# cutdown.net
KiCad netlist of a schematic drawn in EAGLE
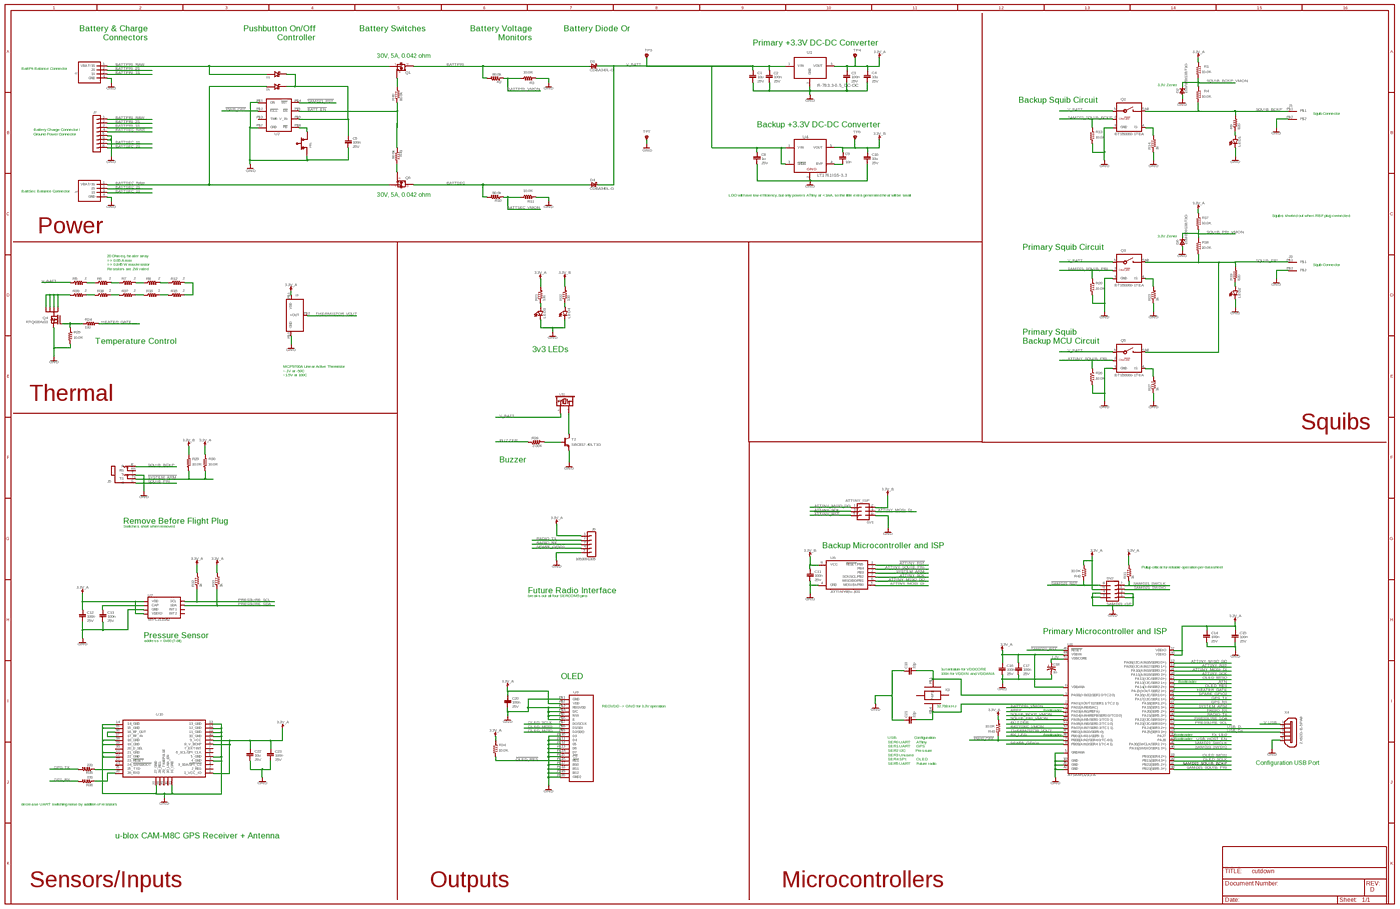
[diagram p0: schematic, sheet 1, overview]
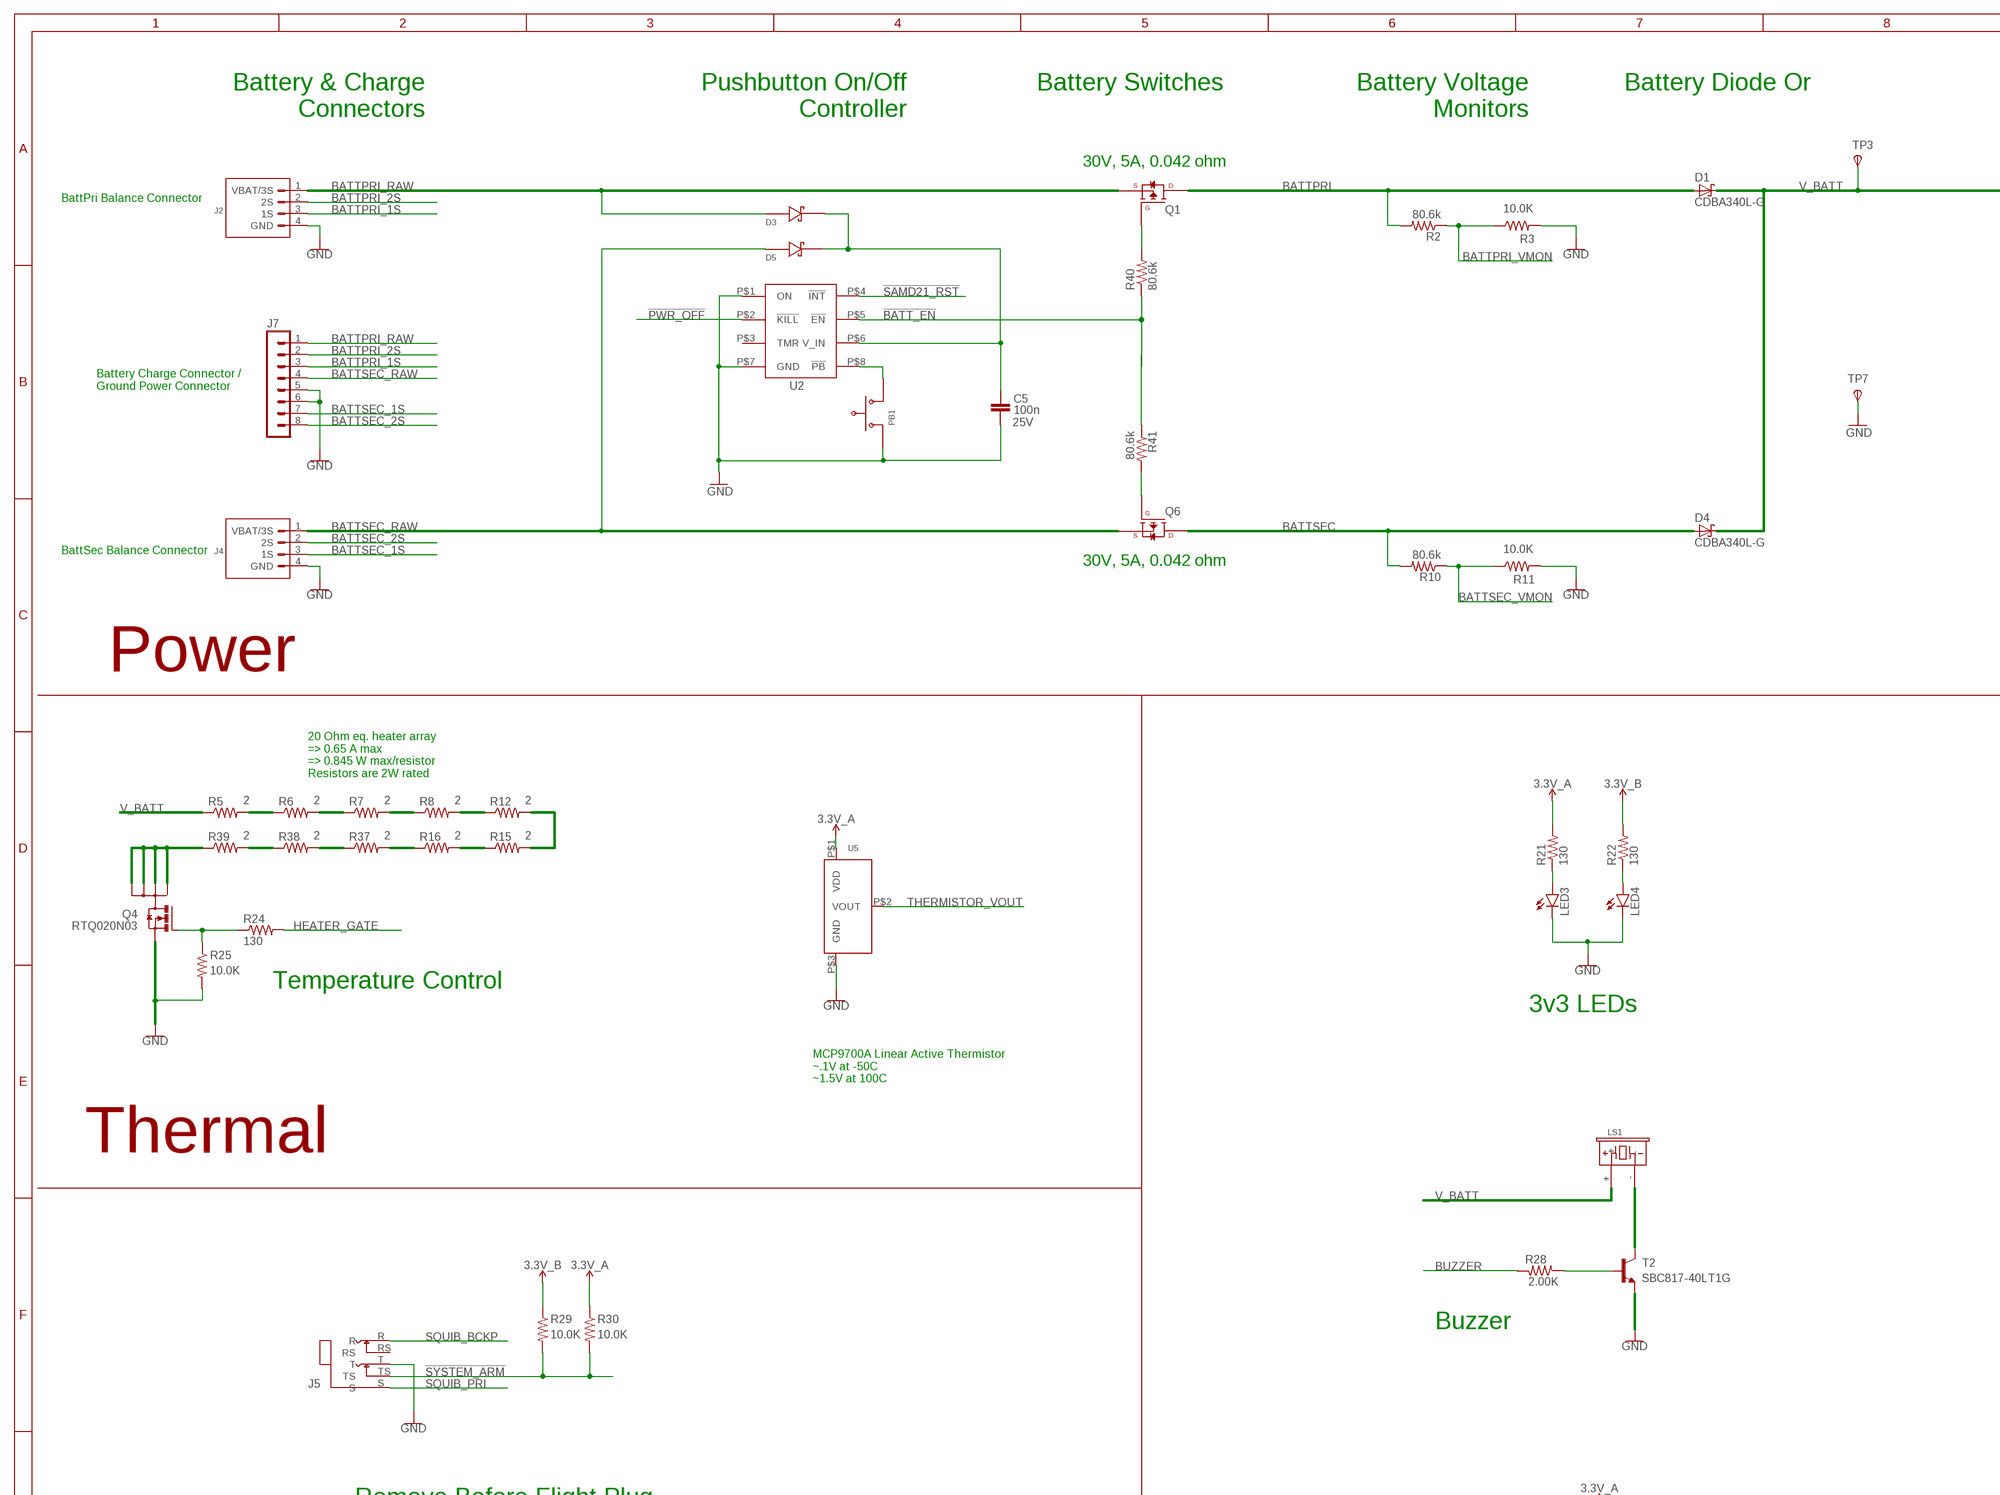
[diagram p1: schematic, sheet 1, part 1 of 4]
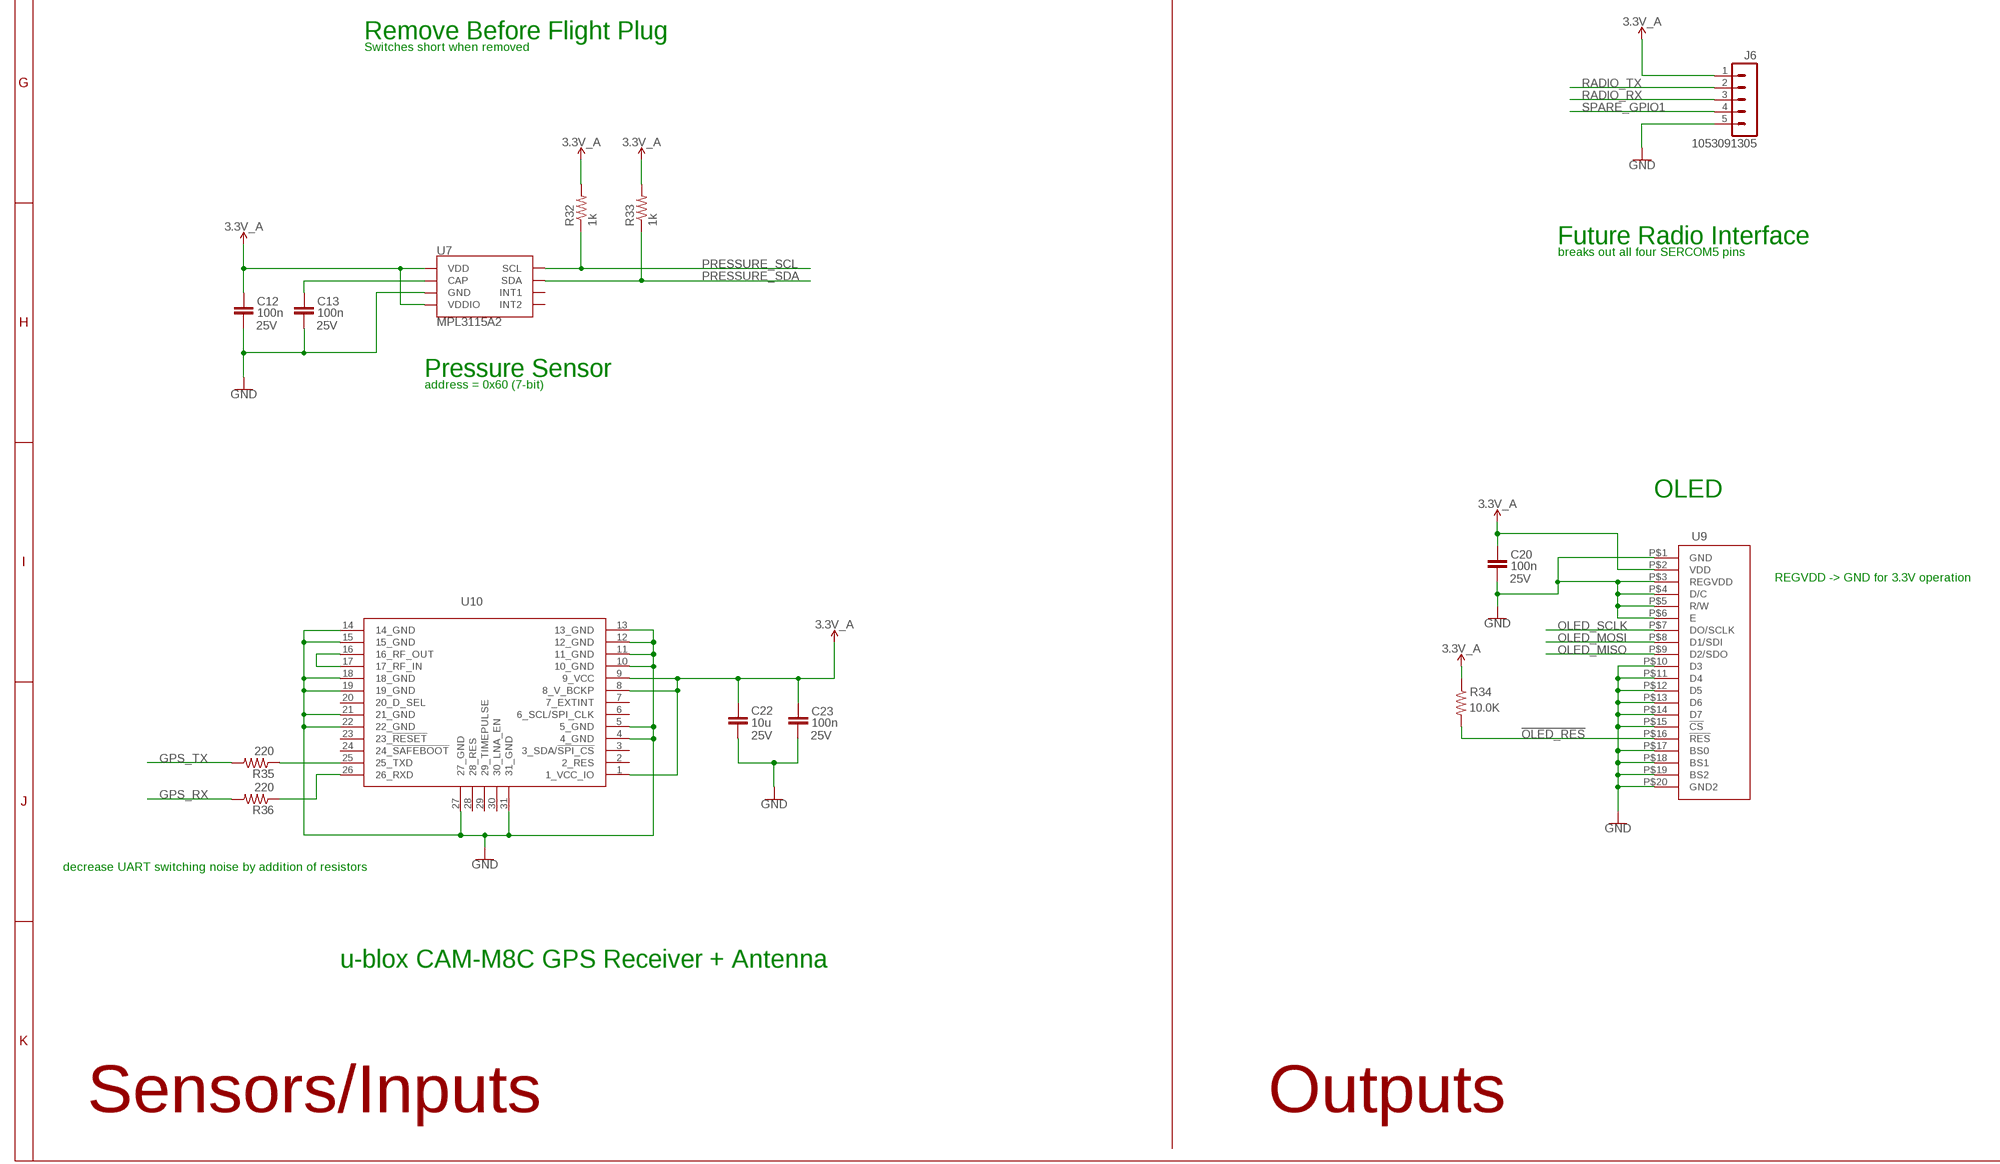
[diagram p2: schematic, sheet 1, part 2 of 4]
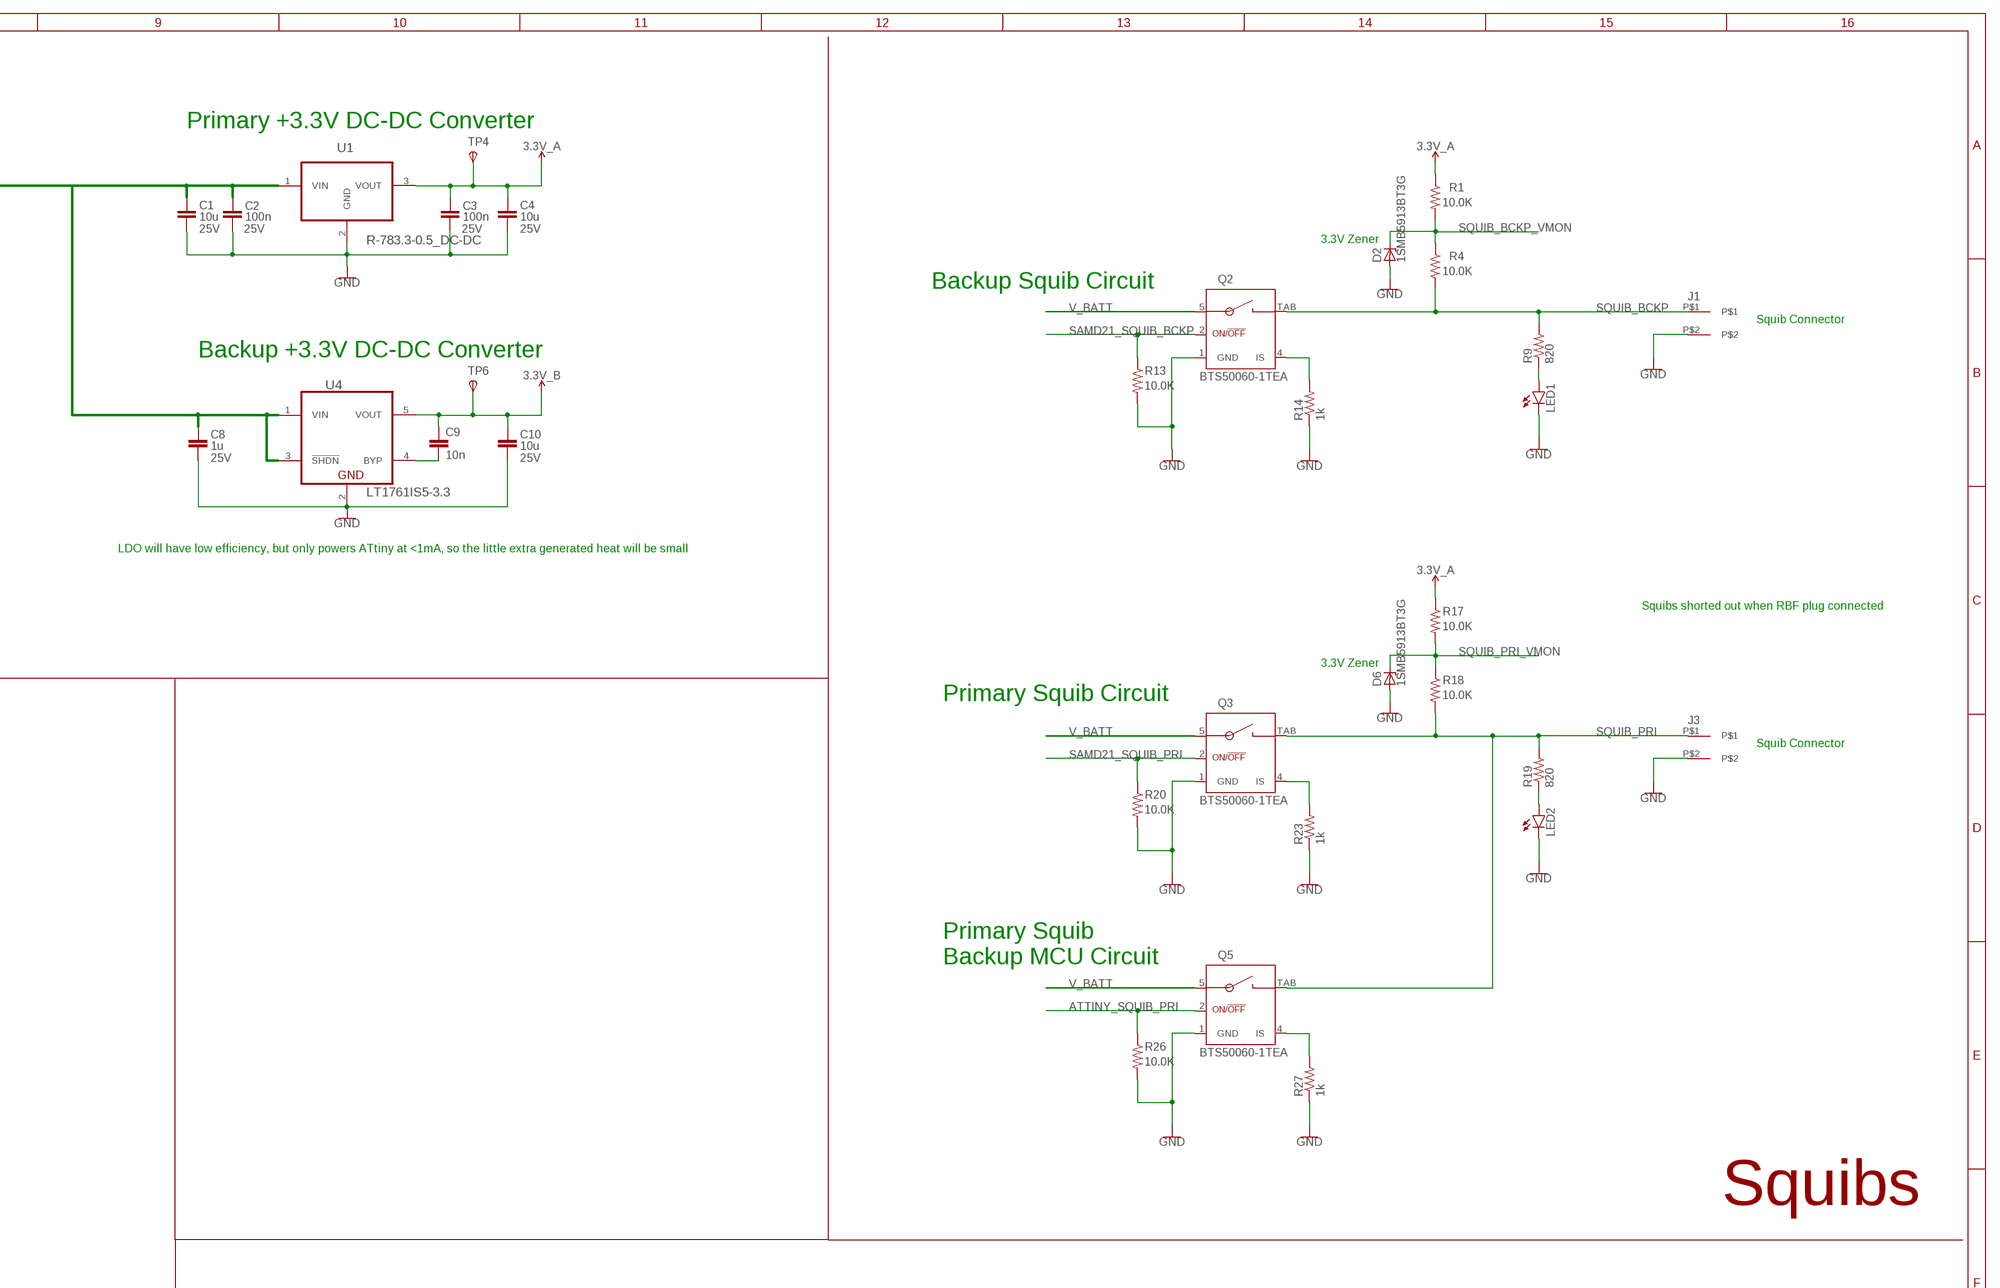
[diagram p3: schematic, sheet 1, part 3 of 4]
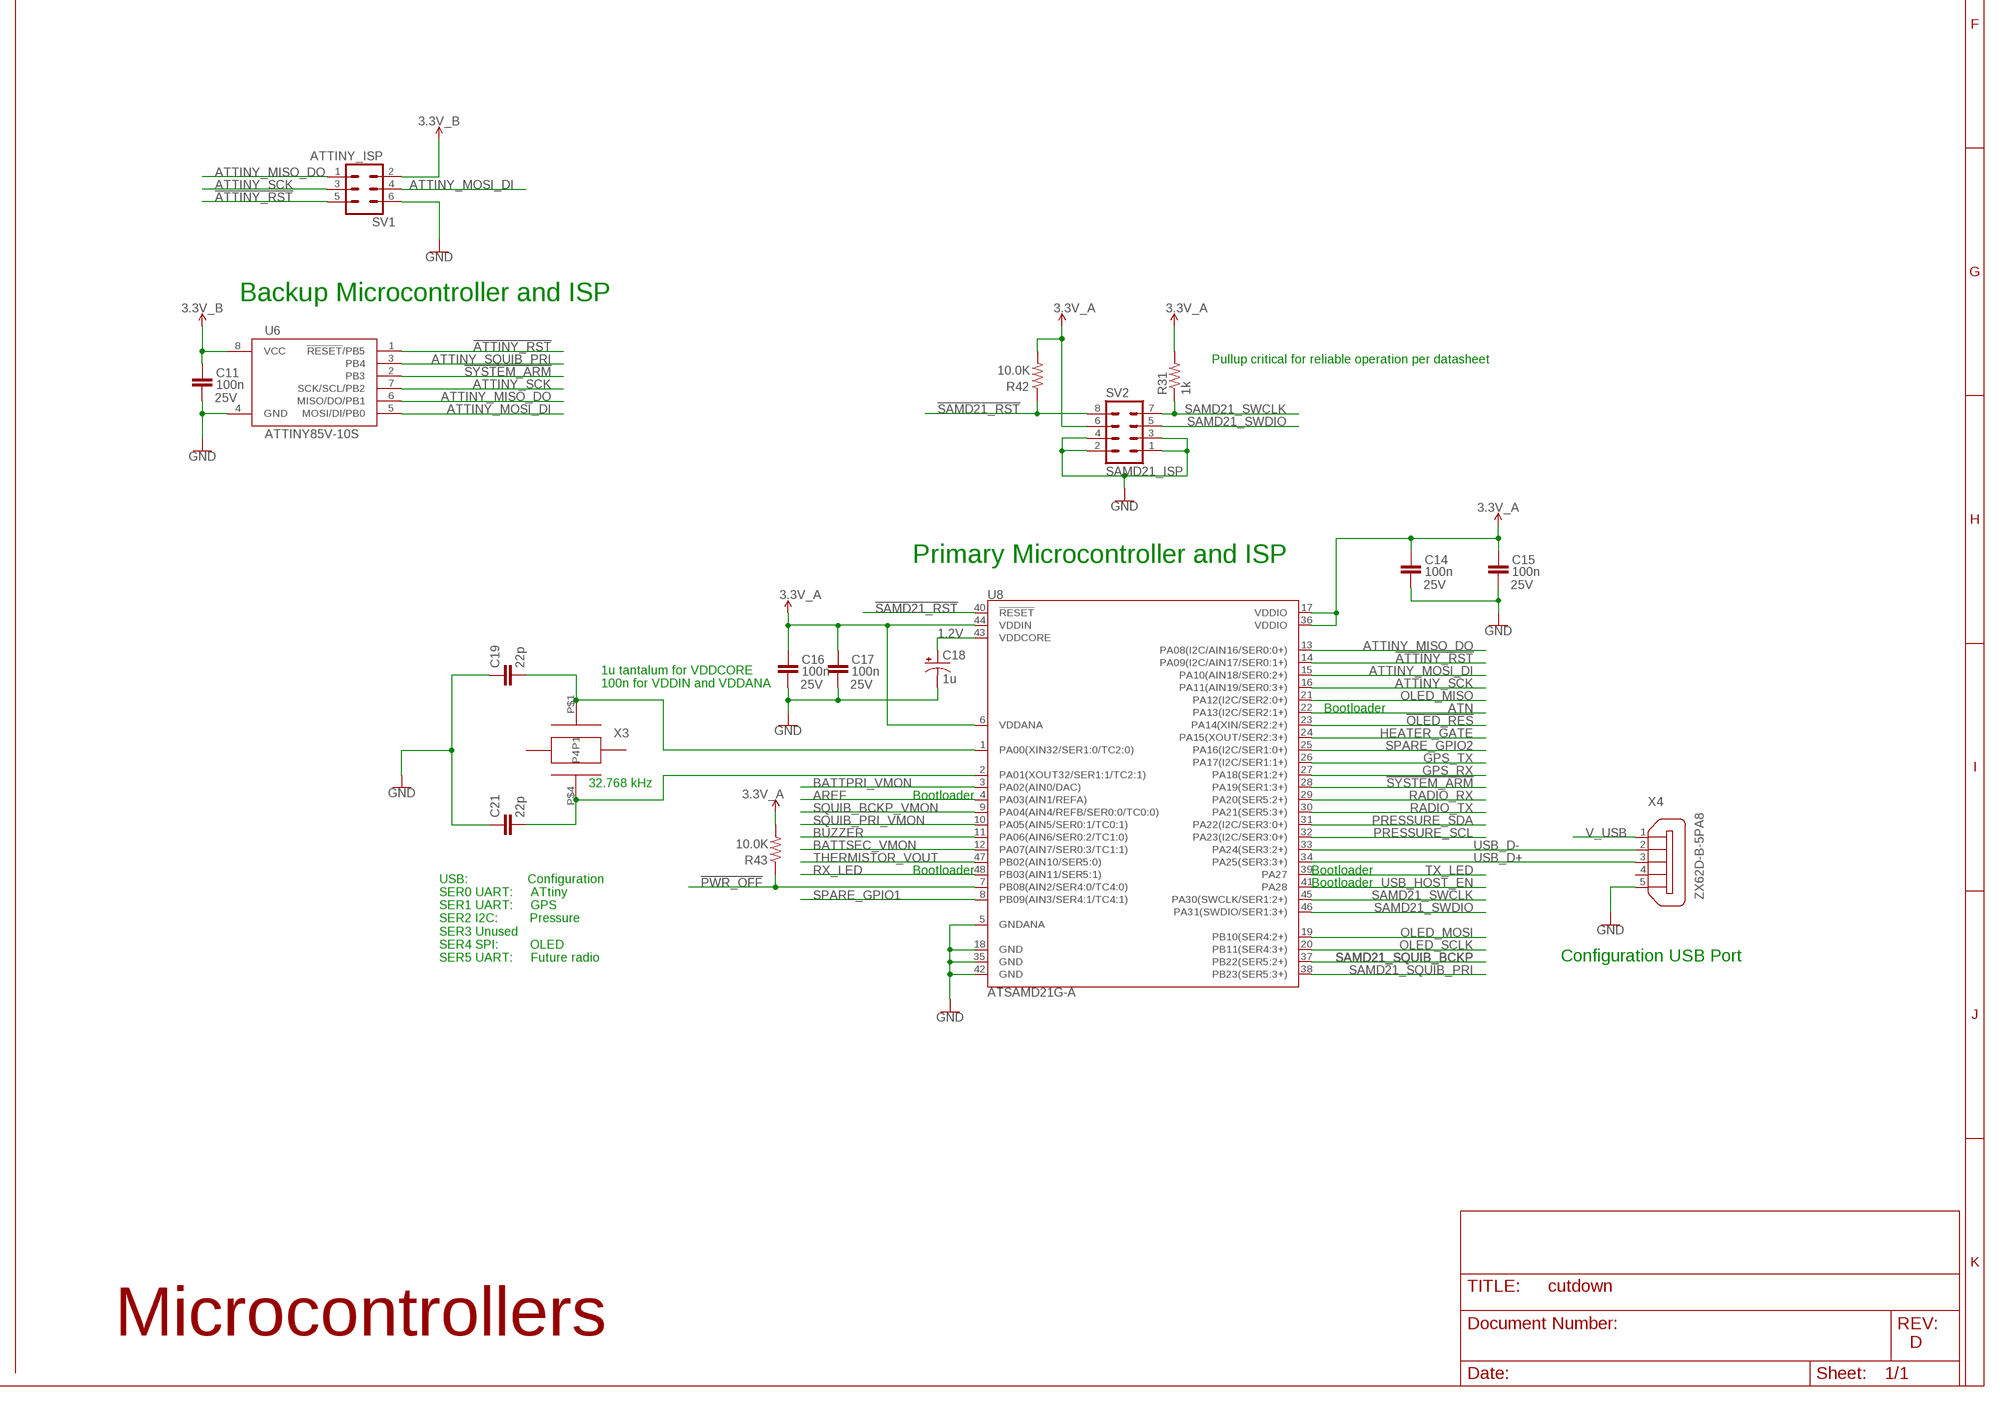
[diagram p4: schematic, sheet 1, part 4 of 4]

(export (version "E")
  (design (tool "Eeschema 10.0.6"))
  (components
    (comp (ref "C1")
      (value "10u")
      (footprint "eagle-import:C1206")
      (fields (field (name "MFG") "Samsung") (field (name "VOLTAGE") "25V"))
      (libsource (lib "eagle-import") (part "C-EUC1206"))
    )
    (comp (ref "C2")
      (value "100n")
      (footprint "eagle-import:C0805")
      (fields (field (name "MFG") "AVX") (field (name "VOLTAGE") "25V"))
      (libsource (lib "eagle-import") (part "resistor_348_C-EUC0805"))
    )
    (comp (ref "C3")
      (value "100n")
      (footprint "eagle-import:C0805")
      (fields (field (name "MFG") "AVX") (field (name "VOLTAGE") "25V"))
      (libsource (lib "eagle-import") (part "resistor_348_C-EUC0805"))
    )
    (comp (ref "C4")
      (value "10u")
      (footprint "eagle-import:C1206")
      (fields (field (name "MFG") "Samsung") (field (name "VOLTAGE") "25V"))
      (libsource (lib "eagle-import") (part "C-EUC1206"))
    )
    (comp (ref "C5")
      (value "100n")
      (footprint "eagle-import:C0805")
      (fields (field (name "MFG") "AVX") (field (name "VOLTAGE") "25V"))
      (libsource (lib "eagle-import") (part "resistor_348_C-EUC0805"))
    )
    (comp (ref "C8")
      (value "1u")
      (footprint "eagle-import:C1206")
      (fields (field (name "MFG") "KEMET") (field (name "VOLTAGE") "25V"))
      (libsource (lib "eagle-import") (part "C-EUC1206"))
    )
    (comp (ref "C9")
      (value "10n")
      (footprint "eagle-import:C0805")
      (fields (field (name "MFG") "Kemet"))
      (libsource (lib "eagle-import") (part "rcl_334_C-EUC0805"))
    )
    (comp (ref "C10")
      (value "10u")
      (footprint "eagle-import:C1206")
      (fields (field (name "MFG") "Samsung") (field (name "VOLTAGE") "25V"))
      (libsource (lib "eagle-import") (part "C-EUC1206"))
    )
    (comp (ref "C11")
      (value "100n")
      (footprint "eagle-import:C0805")
      (fields (field (name "MFG") "AVX") (field (name "VOLTAGE") "25V"))
      (libsource (lib "eagle-import") (part "resistor_348_C-EUC0805"))
    )
    (comp (ref "C12")
      (value "100n")
      (footprint "eagle-import:C0805")
      (fields (field (name "MFG") "AVX") (field (name "VOLTAGE") "25V"))
      (libsource (lib "eagle-import") (part "resistor_348_C-EUC0805"))
    )
    (comp (ref "C13")
      (value "100n")
      (footprint "eagle-import:C0805")
      (fields (field (name "MFG") "AVX") (field (name "VOLTAGE") "25V"))
      (libsource (lib "eagle-import") (part "resistor_348_C-EUC0805"))
    )
    (comp (ref "C14")
      (value "100n")
      (footprint "eagle-import:C0805")
      (fields (field (name "MFG") "AVX") (field (name "VOLTAGE") "25V"))
      (libsource (lib "eagle-import") (part "resistor_348_C-EUC0805"))
    )
    (comp (ref "C15")
      (value "100n")
      (footprint "eagle-import:C0805")
      (fields (field (name "MFG") "AVX") (field (name "VOLTAGE") "25V"))
      (libsource (lib "eagle-import") (part "resistor_348_C-EUC0805"))
    )
    (comp (ref "C16")
      (value "100n")
      (footprint "eagle-import:C0805")
      (fields (field (name "MFG") "AVX") (field (name "VOLTAGE") "25V"))
      (libsource (lib "eagle-import") (part "resistor_348_C-EUC0805"))
    )
    (comp (ref "C17")
      (value "100n")
      (footprint "eagle-import:C0805")
      (fields (field (name "MFG") "AVX") (field (name "VOLTAGE") "25V"))
      (libsource (lib "eagle-import") (part "resistor_348_C-EUC0805"))
    )
    (comp (ref "C18")
      (value "1u")
      (footprint "eagle-import:CT3216")
      (fields (field (name "MFG") "Kemet"))
      (libsource (lib "eagle-import") (part "CPOL-USCT3216"))
    )
    (comp (ref "C19")
      (value "22p")
      (footprint "eagle-import:C0805")
      (fields (field (name "MFG") "Kemet"))
      (libsource (lib "eagle-import") (part "rcl_334_C-EUC0805"))
    )
    (comp (ref "C20")
      (value "100n")
      (footprint "eagle-import:C0805")
      (fields (field (name "MFG") "AVX") (field (name "VOLTAGE") "25V"))
      (libsource (lib "eagle-import") (part "resistor_348_C-EUC0805"))
    )
    (comp (ref "C21")
      (value "22p")
      (footprint "eagle-import:C0805")
      (fields (field (name "MFG") "Kemet"))
      (libsource (lib "eagle-import") (part "rcl_334_C-EUC0805"))
    )
    (comp (ref "C22")
      (value "10u")
      (footprint "eagle-import:C1206")
      (fields (field (name "MFG") "Samsung") (field (name "VOLTAGE") "25V"))
      (libsource (lib "eagle-import") (part "C-EUC1206"))
    )
    (comp (ref "C23")
      (value "100n")
      (footprint "eagle-import:C0805")
      (fields (field (name "MFG") "AVX") (field (name "VOLTAGE") "25V"))
      (libsource (lib "eagle-import") (part "resistor_348_C-EUC0805"))
    )
    (comp (ref "D1")
      (value "CDBA340L-G")
      (footprint "eagle-import:DO214AC")
      (fields (field (name "MFG") "COMCHIP"))
      (libsource (lib "eagle-import") (part "CDBA340L-G"))
    )
    (comp (ref "D2")
      (value "1SMB5913BT3G")
      (footprint "eagle-import:DO214AA")
      (fields (field (name "MF") "ON Semiconductor"))
      (libsource (lib "eagle-import") (part "1SMB59BT3G13"))
    )
    (comp (ref "D3")
      (value "BAT54HT1G")
      (footprint "eagle-import:BAT54HT1G")
      (fields (field (name "MFG") "ON Semiconductor"))
      (libsource (lib "eagle-import") (part "BAT54HT1G"))
    )
    (comp (ref "D4")
      (value "CDBA340L-G")
      (footprint "eagle-import:DO214AC")
      (fields (field (name "MFG") "COMCHIP"))
      (libsource (lib "eagle-import") (part "CDBA340L-G"))
    )
    (comp (ref "D5")
      (value "BAT54HT1G")
      (footprint "eagle-import:BAT54HT1G")
      (fields (field (name "MFG") "ON Semiconductor"))
      (libsource (lib "eagle-import") (part "BAT54HT1G"))
    )
    (comp (ref "D6")
      (value "1SMB5913BT3G")
      (footprint "eagle-import:DO214AA")
      (fields (field (name "MF") "ON Semiconductor"))
      (libsource (lib "eagle-import") (part "1SMB59BT3G13"))
    )
    (comp (ref "J1")
      (value "DECTOR_PARTS_TR_NANOFIT_1X2_RA")
      (footprint "eagle-import:DECTOR_PARTS_TR_NANOFIT_1X2_RIGHTANGLE")
      (fields (field (name "MFG") "Molex"))
      (libsource (lib "eagle-import") (part "DECTOR_PARTS_TR_NANOFIT_1X2_RA"))
    )
    (comp (ref "J2")
      (value "S4B-XH-SM4-TB-3S-BALANCE")
      (footprint "eagle-import:S4B-XH-SM4-TB")
      (fields (field (name "MFG") "JST Sales America Inc."))
      (libsource (lib "eagle-import") (part "S4B-XH-SM4-TB-3S-BALANCE"))
    )
    (comp (ref "J3")
      (value "DECTOR_PARTS_TR_NANOFIT_1X2_RA")
      (footprint "eagle-import:DECTOR_PARTS_TR_NANOFIT_1X2_RIGHTANGLE")
      (fields (field (name "MFG") "Molex"))
      (libsource (lib "eagle-import") (part "DECTOR_PARTS_TR_NANOFIT_1X2_RA"))
    )
    (comp (ref "J4")
      (value "S4B-XH-SM4-TB-3S-BALANCE")
      (footprint "eagle-import:S4B-XH-SM4-TB")
      (fields (field (name "MFG") "JST Sales America Inc."))
      (libsource (lib "eagle-import") (part "S4B-XH-SM4-TB-3S-BALANCE"))
    )
    (comp (ref "J5")
      (value "RN114BPC")
      (footprint "eagle-import:RN114BPC")
      (fields (field (name "MFG") "Switchcraft Inc."))
      (libsource (lib "eagle-import") (part "RN114BPC"))
    )
    (comp (ref "J6")
      (value "1053091305")
      (footprint "eagle-import:1053091305")
      (fields (field (name "MFG") "MOLEX"))
      (libsource (lib "eagle-import") (part "1053091305"))
    )
    (comp (ref "J7")
      (value "1053141208")
      (footprint "eagle-import:1053141208")
      (fields (field (name "MFG") "Molex"))
      (libsource (lib "eagle-import") (part "1053141208"))
    )
    (comp (ref "LED1")
      (value "LEDCHIP-LED0805")
      (footprint "eagle-import:CHIP-LED0805")
      (fields (field (name "MFG") "Lite-On"))
      (libsource (lib "eagle-import") (part "LEDCHIP-LED0805"))
    )
    (comp (ref "LED2")
      (value "LEDCHIP-LED0805")
      (footprint "eagle-import:CHIP-LED0805")
      (fields (field (name "MFG") "Lite-On"))
      (libsource (lib "eagle-import") (part "LEDCHIP-LED0805"))
    )
    (comp (ref "LED3")
      (value "LEDCHIP-LED0805")
      (footprint "eagle-import:CHIP-LED0805")
      (fields (field (name "MFG") "Lite-On"))
      (libsource (lib "eagle-import") (part "LEDCHIP-LED0805"))
    )
    (comp (ref "LED4")
      (value "LEDCHIP-LED0805")
      (footprint "eagle-import:CHIP-LED0805")
      (fields (field (name "MFG") "Lite-On"))
      (libsource (lib "eagle-import") (part "LEDCHIP-LED0805"))
    )
    (comp (ref "LS1")
      (value "CEM-1212C")
      (footprint "eagle-import:CEM-1212C")
      (fields (field (name "MFG") "CUI Devices"))
      (libsource (lib "eagle-import") (part "CEM-1212C"))
    )
    (comp (ref "PB1")
      (value "FP11SPA1B1TP03")
      (footprint "eagle-import:FP11SPA1B1TP03")
      (fields (field (name "MFG") "C&G"))
      (libsource (lib "eagle-import") (part "FP11SPA1B1TP03"))
    )
    (comp (ref "Q1")
      (value "SI2347DS-T1-GE3")
      (footprint "eagle-import:SI1247DS")
      (fields (field (name "MFG") "Vishay Siliconix"))
      (libsource (lib "eagle-import") (part "SI2347DS-T1-GE3"))
    )
    (comp (ref "Q2")
      (value "BTS50060-1TEA")
      (footprint "eagle-import:PG-TO252-5-11")
      (fields (field (name "MFG") "Infineon"))
      (libsource (lib "eagle-import") (part "BTS50060-1TEA"))
    )
    (comp (ref "Q3")
      (value "BTS50060-1TEA")
      (footprint "eagle-import:PG-TO252-5-11")
      (fields (field (name "MFG") "Infineon"))
      (libsource (lib "eagle-import") (part "BTS50060-1TEA"))
    )
    (comp (ref "Q4")
      (value "RTQ020N03")
      (footprint "eagle-import:SC-95(TSMT6)")
      (fields (field (name "MFG") "Rohm"))
      (libsource (lib "eagle-import") (part "RTQ020N03"))
    )
    (comp (ref "Q5")
      (value "BTS50060-1TEA")
      (footprint "eagle-import:PG-TO252-5-11")
      (fields (field (name "MFG") "Infineon"))
      (libsource (lib "eagle-import") (part "BTS50060-1TEA"))
    )
    (comp (ref "Q6")
      (value "SI2347DS-T1-GE3")
      (footprint "eagle-import:SI1247DS")
      (fields (field (name "MFG") "Vishay Siliconix"))
      (libsource (lib "eagle-import") (part "SI2347DS-T1-GE3"))
    )
    (comp (ref "R1")
      (value "10.0K")
      (footprint "eagle-import:R0805")
      (fields (field (name "MFG") "Panasonic"))
      (libsource (lib "eagle-import") (part "resistor_348_R-US_R0805"))
    )
    (comp (ref "R2")
      (value "80.6k")
      (footprint "eagle-import:R0805")
      (fields (field (name "MFG") "Panasonic"))
      (libsource (lib "eagle-import") (part "R-US_R0805"))
    )
    (comp (ref "R3")
      (value "10.0K")
      (footprint "eagle-import:R0805")
      (fields (field (name "MFG") "Panasonic"))
      (libsource (lib "eagle-import") (part "resistor_348_R-US_R0805"))
    )
    (comp (ref "R4")
      (value "10.0K")
      (footprint "eagle-import:R0805")
      (fields (field (name "MFG") "Panasonic"))
      (libsource (lib "eagle-import") (part "resistor_348_R-US_R0805"))
    )
    (comp (ref "R5")
      (value "2")
      (footprint "eagle-import:R2512")
      (fields (field (name "MFG") "Bourns Inc."))
      (libsource (lib "eagle-import") (part "resistor_348_R-US_R2512"))
    )
    (comp (ref "R6")
      (value "2")
      (footprint "eagle-import:R2512")
      (fields (field (name "MFG") "Bourns Inc."))
      (libsource (lib "eagle-import") (part "resistor_348_R-US_R2512"))
    )
    (comp (ref "R7")
      (value "2")
      (footprint "eagle-import:R2512")
      (fields (field (name "MFG") "Bourns Inc."))
      (libsource (lib "eagle-import") (part "resistor_348_R-US_R2512"))
    )
    (comp (ref "R8")
      (value "2")
      (footprint "eagle-import:R2512")
      (fields (field (name "MFG") "Bourns Inc."))
      (libsource (lib "eagle-import") (part "resistor_348_R-US_R2512"))
    )
    (comp (ref "R9")
      (value "820")
      (footprint "eagle-import:R0805")
      (fields (field (name "MFG") "Panasonic"))
      (libsource (lib "eagle-import") (part "R-US_R0805"))
    )
    (comp (ref "R10")
      (value "80.6k")
      (footprint "eagle-import:R0805")
      (fields (field (name "MFG") "Panasonic"))
      (libsource (lib "eagle-import") (part "R-US_R0805"))
    )
    (comp (ref "R11")
      (value "10.0K")
      (footprint "eagle-import:R0805")
      (fields (field (name "MFG") "Panasonic"))
      (libsource (lib "eagle-import") (part "resistor_348_R-US_R0805"))
    )
    (comp (ref "R12")
      (value "2")
      (footprint "eagle-import:R2512")
      (fields (field (name "MFG") "Bourns Inc."))
      (libsource (lib "eagle-import") (part "resistor_348_R-US_R2512"))
    )
    (comp (ref "R13")
      (value "10.0K")
      (footprint "eagle-import:R0805")
      (fields (field (name "MFG") "Panasonic"))
      (libsource (lib "eagle-import") (part "resistor_348_R-US_R0805"))
    )
    (comp (ref "R14")
      (value "1k")
      (footprint "eagle-import:R0805")
      (fields (field (name "MFG") "Panasonic"))
      (libsource (lib "eagle-import") (part "R-US_R0805"))
    )
    (comp (ref "R15")
      (value "2")
      (footprint "eagle-import:R2512")
      (fields (field (name "MFG") "Bourns Inc."))
      (libsource (lib "eagle-import") (part "resistor_348_R-US_R2512"))
    )
    (comp (ref "R16")
      (value "2")
      (footprint "eagle-import:R2512")
      (fields (field (name "MFG") "Bourns Inc."))
      (libsource (lib "eagle-import") (part "resistor_348_R-US_R2512"))
    )
    (comp (ref "R17")
      (value "10.0K")
      (footprint "eagle-import:R0805")
      (fields (field (name "MFG") "Panasonic"))
      (libsource (lib "eagle-import") (part "resistor_348_R-US_R0805"))
    )
    (comp (ref "R18")
      (value "10.0K")
      (footprint "eagle-import:R0805")
      (fields (field (name "MFG") "Panasonic"))
      (libsource (lib "eagle-import") (part "resistor_348_R-US_R0805"))
    )
    (comp (ref "R19")
      (value "820")
      (footprint "eagle-import:R0805")
      (fields (field (name "MFG") "Panasonic"))
      (libsource (lib "eagle-import") (part "R-US_R0805"))
    )
    (comp (ref "R20")
      (value "10.0K")
      (footprint "eagle-import:R0805")
      (fields (field (name "MFG") "Panasonic"))
      (libsource (lib "eagle-import") (part "resistor_348_R-US_R0805"))
    )
    (comp (ref "R21")
      (value "130")
      (footprint "eagle-import:R0805")
      (fields (field (name "MFG") "Panasonic"))
      (libsource (lib "eagle-import") (part "R-US_R0805"))
    )
    (comp (ref "R22")
      (value "130")
      (footprint "eagle-import:R0805")
      (fields (field (name "MFG") "Panasonic"))
      (libsource (lib "eagle-import") (part "R-US_R0805"))
    )
    (comp (ref "R23")
      (value "1k")
      (footprint "eagle-import:R0805")
      (fields (field (name "MFG") "Panasonic"))
      (libsource (lib "eagle-import") (part "R-US_R0805"))
    )
    (comp (ref "R24")
      (value "130")
      (footprint "eagle-import:R0805")
      (fields (field (name "MFG") "Panasonic"))
      (libsource (lib "eagle-import") (part "R-US_R0805"))
    )
    (comp (ref "R25")
      (value "10.0K")
      (footprint "eagle-import:R0805")
      (fields (field (name "MFG") "Panasonic"))
      (libsource (lib "eagle-import") (part "resistor_348_R-US_R0805"))
    )
    (comp (ref "R26")
      (value "10.0K")
      (footprint "eagle-import:R0805")
      (fields (field (name "MFG") "Panasonic"))
      (libsource (lib "eagle-import") (part "resistor_348_R-US_R0805"))
    )
    (comp (ref "R27")
      (value "1k")
      (footprint "eagle-import:R0805")
      (fields (field (name "MFG") "Panasonic"))
      (libsource (lib "eagle-import") (part "R-US_R0805"))
    )
    (comp (ref "R28")
      (value "2.00K")
      (footprint "eagle-import:R0805")
      (fields (field (name "MFG") "Panasonic"))
      (libsource (lib "eagle-import") (part "resistor_348_R-US_R0805"))
    )
    (comp (ref "R29")
      (value "10.0K")
      (footprint "eagle-import:R0805")
      (fields (field (name "MFG") "Panasonic"))
      (libsource (lib "eagle-import") (part "resistor_348_R-US_R0805"))
    )
    (comp (ref "R30")
      (value "10.0K")
      (footprint "eagle-import:R0805")
      (fields (field (name "MFG") "Panasonic"))
      (libsource (lib "eagle-import") (part "resistor_348_R-US_R0805"))
    )
    (comp (ref "R31")
      (value "1k")
      (footprint "eagle-import:R0805")
      (fields (field (name "MFG") "Panasonic"))
      (libsource (lib "eagle-import") (part "R-US_R0805"))
    )
    (comp (ref "R32")
      (value "1k")
      (footprint "eagle-import:R0805")
      (fields (field (name "MFG") "Panasonic"))
      (libsource (lib "eagle-import") (part "R-US_R0805"))
    )
    (comp (ref "R33")
      (value "1k")
      (footprint "eagle-import:R0805")
      (fields (field (name "MFG") "Panasonic"))
      (libsource (lib "eagle-import") (part "R-US_R0805"))
    )
    (comp (ref "R34")
      (value "10.0K")
      (footprint "eagle-import:R0805")
      (fields (field (name "MFG") "Panasonic"))
      (libsource (lib "eagle-import") (part "resistor_348_R-US_R0805"))
    )
    (comp (ref "R35")
      (value "220")
      (footprint "eagle-import:R0805")
      (fields (field (name "MFG") "Panasonic"))
      (libsource (lib "eagle-import") (part "R-US_R0805"))
    )
    (comp (ref "R36")
      (value "220")
      (footprint "eagle-import:R0805")
      (fields (field (name "MFG") "Panasonic"))
      (libsource (lib "eagle-import") (part "R-US_R0805"))
    )
    (comp (ref "R37")
      (value "2")
      (footprint "eagle-import:R2512")
      (fields (field (name "MFG") "Bourns Inc."))
      (libsource (lib "eagle-import") (part "resistor_348_R-US_R2512"))
    )
    (comp (ref "R38")
      (value "2")
      (footprint "eagle-import:R2512")
      (fields (field (name "MFG") "Bourns Inc."))
      (libsource (lib "eagle-import") (part "resistor_348_R-US_R2512"))
    )
    (comp (ref "R39")
      (value "2")
      (footprint "eagle-import:R2512")
      (fields (field (name "MFG") "Bourns Inc."))
      (libsource (lib "eagle-import") (part "resistor_348_R-US_R2512"))
    )
    (comp (ref "R40")
      (value "80.6k")
      (footprint "eagle-import:R0805")
      (fields (field (name "MFG") "Panasonic"))
      (libsource (lib "eagle-import") (part "R-US_R0805"))
    )
    (comp (ref "R41")
      (value "80.6k")
      (footprint "eagle-import:R0805")
      (fields (field (name "MFG") "Panasonic"))
      (libsource (lib "eagle-import") (part "R-US_R0805"))
    )
    (comp (ref "R42")
      (value "10.0K")
      (footprint "eagle-import:R0805")
      (fields (field (name "MFG") "Panasonic"))
      (libsource (lib "eagle-import") (part "resistor_348_R-US_R0805"))
    )
    (comp (ref "R43")
      (value "10.0K")
      (footprint "eagle-import:R0805")
      (fields (field (name "MFG") "Panasonic"))
      (libsource (lib "eagle-import") (part "resistor_348_R-US_R0805"))
    )
    (comp (ref "SV1")
      (value "ATTINY_ISP")
      (footprint "eagle-import:MA03-2")
      (fields (field (name "MFG") "Amphenol"))
      (libsource (lib "eagle-import") (part "MA03-2"))
    )
    (comp (ref "SV2")
      (value "SAMD21_ISP")
      (footprint "eagle-import:MA04-2")
      (fields (field (name "MFG") "Amphenol"))
      (libsource (lib "eagle-import") (part "MA04-2"))
    )
    (comp (ref "T2")
      (value "SBC817-40LT1G")
      (footprint "eagle-import:SOT23")
      (fields (field (name "MFG") "On Semi"))
      (libsource (lib "eagle-import") (part "BC846"))
    )
    (comp (ref "TP3")
      (value "TPSPAD1-13")
      (footprint "eagle-import:P1-13")
      (libsource (lib "eagle-import") (part "testpad_385_TPSPAD1-13"))
    )
    (comp (ref "TP4")
      (value "TPSPAD1-13")
      (footprint "eagle-import:P1-13")
      (libsource (lib "eagle-import") (part "testpad_385_TPSPAD1-13"))
    )
    (comp (ref "TP6")
      (value "TPSPAD1-13")
      (footprint "eagle-import:P1-13")
      (libsource (lib "eagle-import") (part "testpad_385_TPSPAD1-13"))
    )
    (comp (ref "TP7")
      (value "TPSPAD1-13")
      (footprint "eagle-import:P1-13")
      (fields (field (name "MFG") "Keystone"))
      (libsource (lib "eagle-import") (part "TPSPAD1-13"))
    )
    (comp (ref "U1")
      (value "R-783.3-0.5_DC-DC")
      (footprint "eagle-import:R-783P3-0P5_DC-DC")
      (fields (field (name "MFG") "RECOM"))
      (libsource (lib "eagle-import") (part "R-783.3-0.5_DC-DC"))
    )
    (comp (ref "U2")
      (value "LTC2955ITS8-2")
      (footprint "eagle-import:LTC2955_TSOT-8")
      (fields (field (name "MFG") "Linear Technology/Analog Devices"))
      (libsource (lib "eagle-import") (part "LTC2955ITS8-2"))
    )
    (comp (ref "U4")
      (value "LT1761IS5-3.3")
      (footprint "eagle-import:TSOT23-5")
      (fields (field (name "MFG") "Linear Technology"))
      (libsource (lib "eagle-import") (part "LT1761IS5-3.3"))
    )
    (comp (ref "U5")
      (value "MCP9700T-E/TT")
      (footprint "eagle-import:MCP9700T-E_TT")
      (fields (field (name "MFG") "Microchip Technology"))
      (libsource (lib "eagle-import") (part "MCP9700T-E/TT"))
    )
    (comp (ref "U6")
      (value "ATTINY85V-10S")
      (footprint "eagle-import:SOIC8_EIAJ_208MIL")
      (fields (field (name "MFG") "Atmel"))
      (libsource (lib "eagle-import") (part "ATTINY85SV-10"))
    )
    (comp (ref "U7")
      (value "MPL3115A2")
      (footprint "eagle-import:LGA-8-5X3")
      (fields (field (name "MFG") "NXP"))
      (libsource (lib "eagle-import") (part "MPL3115A2"))
    )
    (comp (ref "U8")
      (value "ATSAMD21G-A")
      (footprint "eagle-import:TQFP-48")
      (fields (field (name "MFG") "Atmel"))
      (libsource (lib "eagle-import") (part "ATSAMD21G-A"))
    )
    (comp (ref "U9")
      (value "NHD-0216CW-AW3")
      (footprint "eagle-import:NHD-0216CW-AW3")
      (fields (field (name "MFG") "Newhaven"))
      (libsource (lib "eagle-import") (part "NHD-0216CW-AW3"))
    )
    (comp (ref "U10")
      (value "CAM-M8C-0")
      (footprint "eagle-import:CAM_M8C")
      (fields (field (name "MFG") "U-Blox America Inc."))
      (libsource (lib "eagle-import") (part "CAM-M8C-0"))
    )
    (comp (ref "X3")
      (value "MC-146-32.7680KA-A0")
      (footprint "eagle-import:MC-146")
      (fields (field (name "MFG") "Epson"))
      (libsource (lib "eagle-import") (part "MC-146-32.7680KA-A0"))
    )
    (comp (ref "X4")
      (value "ZX62D-B-5PA8")
      (footprint "eagle-import:ZX62D-B-5PA8")
      (fields (field (name "MF") "Hirose"))
      (libsource (lib "eagle-import") (part "ZX62D-B-5PA8"))
    )
  )
  (nets
    (net (code "1") (name "/1.2V") (class "Default")
      (node (ref "C18") (pin "+") (pinfunction "+_+") (pintype "passive"))
      (node (ref "U8") (pin "43") (pinfunction "VDDCORE_43") (pintype "bidirectional"))
    )
    (net (code "2") (name "/AREF") (class "Default")
      (node (ref "U8") (pin "4") (pinfunction "PA03(AIN1/REFA)_4") (pintype "bidirectional"))
    )
    (net (code "3") (name "/ATN") (class "Default")
      (node (ref "U8") (pin "22") (pinfunction "PA13(I2C/SER2:1+)_22") (pintype "bidirectional"))
    )
    (net (code "4") (name "/ATTINY_MISO_DO") (class "Default")
      (node (ref "SV1") (pin "1") (pinfunction "1_1") (pintype "passive"))
      (node (ref "U6") (pin "6") (pinfunction "MISO/DO/PB1_6") (pintype "bidirectional"))
      (node (ref "U8") (pin "13") (pinfunction "PA08(I2C/AIN16/SER0:0+)_13") (pintype "bidirectional"))
    )
    (net (code "5") (name "/ATTINY_MOSI_DI") (class "Default")
      (node (ref "SV1") (pin "4") (pinfunction "4_4") (pintype "passive"))
      (node (ref "U6") (pin "5") (pinfunction "MOSI/DI/PB0_5") (pintype "bidirectional"))
      (node (ref "U8") (pin "15") (pinfunction "PA10(AIN18/SER0:2+)_15") (pintype "bidirectional"))
    )
    (net (code "6") (name "/ATTINY_SCK") (class "Default")
      (node (ref "SV1") (pin "3") (pinfunction "3_3") (pintype "passive"))
      (node (ref "U6") (pin "7") (pinfunction "SCK/SCL/PB2_7") (pintype "bidirectional"))
      (node (ref "U8") (pin "16") (pinfunction "PA11(AIN19/SER0:3+)_16") (pintype "bidirectional"))
    )
    (net (code "7") (name "/ATTINY_SQUIB_PRI") (class "Default")
      (node (ref "Q5") (pin "2") (pinfunction "IN_2") (pintype "input"))
      (node (ref "R26") (pin "1") (pinfunction "1_1") (pintype "passive"))
      (node (ref "U6") (pin "3") (pinfunction "PB4_3") (pintype "bidirectional"))
    )
    (net (code "8") (name "/BATTPRI") (class "Default")
      (node (ref "D1") (pin "A") (pinfunction "A_A") (pintype "passive"))
      (node (ref "Q1") (pin "D") (pinfunction "D_D") (pintype "bidirectional"))
      (node (ref "R2") (pin "2") (pinfunction "2_2") (pintype "passive"))
    )
    (net (code "9") (name "/BATTPRI_1S") (class "Default")
      (node (ref "J2") (pin "3") (pinfunction "1S_3") (pintype "bidirectional"))
      (node (ref "J7") (pin "3") (pinfunction "3_3") (pintype "passive"))
    )
    (net (code "10") (name "/BATTPRI_2S") (class "Default")
      (node (ref "J2") (pin "2") (pinfunction "2S_2") (pintype "bidirectional"))
      (node (ref "J7") (pin "2") (pinfunction "2_2") (pintype "passive"))
    )
    (net (code "11") (name "/BATTPRI_RAW") (class "Default")
      (node (ref "D3") (pin "A") (pinfunction "A_A") (pintype "bidirectional"))
      (node (ref "J2") (pin "1") (pinfunction "VBAT/3S_1") (pintype "bidirectional"))
      (node (ref "J7") (pin "1") (pinfunction "1_1") (pintype "passive"))
      (node (ref "Q1") (pin "S") (pinfunction "S_S") (pintype "bidirectional"))
    )
    (net (code "12") (name "/BATTPRI_VMON") (class "Default")
      (node (ref "R2") (pin "1") (pinfunction "1_1") (pintype "passive"))
      (node (ref "R3") (pin "1") (pinfunction "1_1") (pintype "passive"))
      (node (ref "U8") (pin "3") (pinfunction "PA02(AIN0/DAC)_3") (pintype "bidirectional"))
    )
    (net (code "13") (name "/BATTSEC") (class "Default")
      (node (ref "D4") (pin "A") (pinfunction "A_A") (pintype "passive"))
      (node (ref "Q6") (pin "D") (pinfunction "D_D") (pintype "bidirectional"))
      (node (ref "R10") (pin "2") (pinfunction "2_2") (pintype "passive"))
    )
    (net (code "14") (name "/BATTSEC_1S") (class "Default")
      (node (ref "J4") (pin "3") (pinfunction "1S_3") (pintype "bidirectional"))
      (node (ref "J7") (pin "7") (pinfunction "7_7") (pintype "passive"))
    )
    (net (code "15") (name "/BATTSEC_2S") (class "Default")
      (node (ref "J4") (pin "2") (pinfunction "2S_2") (pintype "bidirectional"))
      (node (ref "J7") (pin "8") (pinfunction "8_8") (pintype "passive"))
    )
    (net (code "16") (name "/BATTSEC_RAW") (class "Default")
      (node (ref "D5") (pin "A") (pinfunction "A_A") (pintype "bidirectional"))
      (node (ref "J4") (pin "1") (pinfunction "VBAT/3S_1") (pintype "bidirectional"))
      (node (ref "J7") (pin "4") (pinfunction "4_4") (pintype "passive"))
      (node (ref "Q6") (pin "S") (pinfunction "S_S") (pintype "bidirectional"))
    )
    (net (code "17") (name "/BATTSEC_VMON") (class "Default")
      (node (ref "R10") (pin "1") (pinfunction "1_1") (pintype "passive"))
      (node (ref "R11") (pin "1") (pinfunction "1_1") (pintype "passive"))
      (node (ref "U8") (pin "12") (pinfunction "PA07(AIN7/SER0:3/TC1:1)_12") (pintype "bidirectional"))
    )
    (net (code "18") (name "/BUZZER") (class "Default")
      (node (ref "R28") (pin "2") (pinfunction "2_2") (pintype "passive"))
      (node (ref "U8") (pin "11") (pinfunction "PA06(AIN6/SER0:2/TC1:0)_11") (pintype "bidirectional"))
    )
    (net (code "19") (name "/GPS_RX") (class "Default")
      (node (ref "R36") (pin "2") (pinfunction "2_2") (pintype "passive"))
      (node (ref "U8") (pin "27") (pinfunction "PA18(SER1:2+)_27") (pintype "bidirectional"))
    )
    (net (code "20") (name "/GPS_TX") (class "Default")
      (node (ref "R35") (pin "2") (pinfunction "2_2") (pintype "passive"))
      (node (ref "U8") (pin "26") (pinfunction "PA17(I2C/SER1:1+)_26") (pintype "bidirectional"))
    )
    (net (code "21") (name "/HEATER_GATE") (class "Default")
      (node (ref "R24") (pin "2") (pinfunction "2_2") (pintype "passive"))
      (node (ref "U8") (pin "24") (pinfunction "PA15(XOUT/SER2:3+)_24") (pintype "bidirectional"))
    )
    (net (code "22") (name "/OLED_MISO") (class "Default")
      (node (ref "U8") (pin "21") (pinfunction "PA12(I2C/SER2:0+)_21") (pintype "bidirectional"))
      (node (ref "U9") (pin "P$9") (pinfunction "D2/SDO_P$9") (pintype "bidirectional"))
    )
    (net (code "23") (name "/OLED_MOSI") (class "Default")
      (node (ref "U8") (pin "19") (pinfunction "PB10(SER4:2+)_19") (pintype "bidirectional"))
      (node (ref "U9") (pin "P$8") (pinfunction "D1/SDI_P$8") (pintype "bidirectional"))
    )
    (net (code "24") (name "/OLED_SCLK") (class "Default")
      (node (ref "U8") (pin "20") (pinfunction "PB11(SER4:3+)_20") (pintype "bidirectional"))
      (node (ref "U9") (pin "P$7") (pinfunction "DO/SCLK_P$7") (pintype "bidirectional"))
    )
    (net (code "25") (name "/PRESSURE_SCL") (class "Default")
      (node (ref "R32") (pin "1") (pinfunction "1_1") (pintype "passive"))
      (node (ref "U7") (pin "8") (pinfunction "SCL_8") (pintype "bidirectional"))
      (node (ref "U8") (pin "32") (pinfunction "PA23(I2C/SER3:0+)_32") (pintype "bidirectional"))
    )
    (net (code "26") (name "/PRESSURE_SDA") (class "Default")
      (node (ref "R33") (pin "1") (pinfunction "1_1") (pintype "passive"))
      (node (ref "U7") (pin "7") (pinfunction "SDA_7") (pintype "bidirectional"))
      (node (ref "U8") (pin "31") (pinfunction "PA22(I2C/SER3:0+)_31") (pintype "bidirectional"))
    )
    (net (code "27") (name "/RADIO_RX") (class "Default")
      (node (ref "J6") (pin "3") (pinfunction "3_3") (pintype "passive"))
      (node (ref "U8") (pin "29") (pinfunction "PA20(SER5:2+)_29") (pintype "bidirectional"))
    )
    (net (code "28") (name "/RADIO_TX") (class "Default")
      (node (ref "J6") (pin "2") (pinfunction "2_2") (pintype "passive"))
      (node (ref "U8") (pin "30") (pinfunction "PA21(SER5:3+)_30") (pintype "bidirectional"))
    )
    (net (code "29") (name "/RX_LED") (class "Default")
      (node (ref "U8") (pin "48") (pinfunction "PB03(AIN11/SER5:1)_48") (pintype "bidirectional"))
    )
    (net (code "30") (name "/SAMD21_SQUIB_BCKP") (class "Default")
      (node (ref "Q2") (pin "2") (pinfunction "IN_2") (pintype "input"))
      (node (ref "R13") (pin "1") (pinfunction "1_1") (pintype "passive"))
      (node (ref "U8") (pin "37") (pinfunction "PB22(SER5:2+)_37") (pintype "bidirectional"))
    )
    (net (code "31") (name "/SAMD21_SQUIB_PRI") (class "Default")
      (node (ref "Q3") (pin "2") (pinfunction "IN_2") (pintype "input"))
      (node (ref "R20") (pin "1") (pinfunction "1_1") (pintype "passive"))
      (node (ref "U8") (pin "38") (pinfunction "PB23(SER5:3+)_38") (pintype "bidirectional"))
    )
    (net (code "32") (name "/SAMD21_SWCLK") (class "Default")
      (node (ref "R31") (pin "1") (pinfunction "1_1") (pintype "passive"))
      (node (ref "SV2") (pin "7") (pinfunction "7_7") (pintype "passive"))
      (node (ref "U8") (pin "45") (pinfunction "PA30(SWCLK/SER1:2+)_45") (pintype "bidirectional"))
    )
    (net (code "33") (name "/SAMD21_SWDIO") (class "Default")
      (node (ref "SV2") (pin "5") (pinfunction "5_5") (pintype "passive"))
      (node (ref "U8") (pin "46") (pinfunction "PA31(SWDIO/SER1:3+)_46") (pintype "bidirectional"))
    )
    (net (code "34") (name "/SPARE_GPIO1") (class "Default")
      (node (ref "J6") (pin "4") (pinfunction "4_4") (pintype "passive"))
      (node (ref "U8") (pin "8") (pinfunction "PB09(AIN3/SER4:1/TC4:1)_8") (pintype "bidirectional"))
    )
    (net (code "35") (name "/SPARE_GPIO2") (class "Default")
      (node (ref "U8") (pin "25") (pinfunction "PA16(I2C/SER1:0+)_25") (pintype "bidirectional"))
    )
    (net (code "36") (name "/SQUIB_BCKP") (class "Default")
      (node (ref "J1") (pin "P$1") (pinfunction "P$1_P$1") (pintype "bidirectional"))
      (node (ref "J5") (pin "R") (pinfunction "R_R") (pintype "bidirectional"))
      (node (ref "Q2") (pin "TAB") (pinfunction "OUT_TAB") (pintype "output"))
      (node (ref "R4") (pin "2") (pinfunction "2_2") (pintype "passive"))
      (node (ref "R9") (pin "2") (pinfunction "2_2") (pintype "passive"))
    )
    (net (code "37") (name "/SQUIB_BCKP_VMON") (class "Default")
      (node (ref "D2") (pin "C") (pinfunction "C_C") (pintype "passive"))
      (node (ref "R1") (pin "2") (pinfunction "2_2") (pintype "passive"))
      (node (ref "R4") (pin "1") (pinfunction "1_1") (pintype "passive"))
      (node (ref "U8") (pin "9") (pinfunction "PA04(AIN4/REFB/SER0:0/TC0:0)_9") (pintype "bidirectional"))
    )
    (net (code "38") (name "/SQUIB_PRI") (class "Default")
      (node (ref "J3") (pin "P$1") (pinfunction "P$1_P$1") (pintype "bidirectional"))
      (node (ref "J5") (pin "S") (pinfunction "S_S") (pintype "bidirectional"))
      (node (ref "Q3") (pin "TAB") (pinfunction "OUT_TAB") (pintype "output"))
      (node (ref "Q5") (pin "TAB") (pinfunction "OUT_TAB") (pintype "output"))
      (node (ref "R18") (pin "2") (pinfunction "2_2") (pintype "passive"))
      (node (ref "R19") (pin "2") (pinfunction "2_2") (pintype "passive"))
    )
    (net (code "39") (name "/SQUIB_PRI_VMON") (class "Default")
      (node (ref "D6") (pin "C") (pinfunction "C_C") (pintype "passive"))
      (node (ref "R17") (pin "2") (pinfunction "2_2") (pintype "passive"))
      (node (ref "R18") (pin "1") (pinfunction "1_1") (pintype "passive"))
      (node (ref "U8") (pin "10") (pinfunction "PA05(AIN5/SER0:1/TC0:1)_10") (pintype "bidirectional"))
    )
    (net (code "40") (name "/THERMISTOR_VOUT") (class "Default")
      (node (ref "U5") (pin "P$2") (pinfunction "VOUT_P$2") (pintype "bidirectional"))
      (node (ref "U8") (pin "47") (pinfunction "PB02(AIN10/SER5:0)_47") (pintype "bidirectional"))
    )
    (net (code "41") (name "/TX_LED") (class "Default")
      (node (ref "U8") (pin "39") (pinfunction "PA27_39") (pintype "bidirectional"))
    )
    (net (code "42") (name "/USB_D+") (class "Default")
      (node (ref "U8") (pin "34") (pinfunction "PA25(SER3:3+)_34") (pintype "bidirectional"))
      (node (ref "X4") (pin "3") (pinfunction "3_3") (pintype "passive"))
    )
    (net (code "43") (name "/USB_D-") (class "Default")
      (node (ref "U8") (pin "33") (pinfunction "PA24(SER3:2+)_33") (pintype "bidirectional"))
      (node (ref "X4") (pin "2") (pinfunction "2_2") (pintype "passive"))
    )
    (net (code "44") (name "/USB_HOST_EN") (class "Default")
      (node (ref "U8") (pin "41") (pinfunction "PA28_41") (pintype "bidirectional"))
    )
    (net (code "45") (name "/V_BATT") (class "Default")
      (node (ref "C1") (pin "1") (pinfunction "1_1") (pintype "passive"))
      (node (ref "C2") (pin "1") (pinfunction "1_1") (pintype "passive"))
      (node (ref "C8") (pin "1") (pinfunction "1_1") (pintype "passive"))
      (node (ref "D1") (pin "C") (pinfunction "C_C") (pintype "passive"))
      (node (ref "D4") (pin "C") (pinfunction "C_C") (pintype "passive"))
      (node (ref "LS1") (pin "+") (pinfunction "+_+") (pintype "bidirectional"))
      (node (ref "Q2") (pin "5") (pinfunction "VS_5") (pintype "power_in"))
      (node (ref "Q3") (pin "5") (pinfunction "VS_5") (pintype "power_in"))
      (node (ref "Q5") (pin "5") (pinfunction "VS_5") (pintype "power_in"))
      (node (ref "R5") (pin "1") (pinfunction "1_1") (pintype "passive"))
      (node (ref "TP3") (pin "TP") (pinfunction "PP_TP") (pintype "input"))
      (node (ref "U1") (pin "1") (pinfunction "VIN_1") (pintype "power_in"))
      (node (ref "U4") (pin "1") (pinfunction "VIN_1") (pintype "power_in"))
      (node (ref "U4") (pin "3") (pinfunction "~{SHDN}_3") (pintype "power_in"))
    )
    (net (code "46") (name "/V_USB") (class "Default")
      (node (ref "X4") (pin "1") (pinfunction "1_1") (pintype "passive"))
    )
    (net (code "47") (name "/~{ATTINY_RST}") (class "Default")
      (node (ref "SV1") (pin "5") (pinfunction "5_5") (pintype "passive"))
      (node (ref "U6") (pin "1") (pinfunction "~{RESET}/PB5_1") (pintype "bidirectional"))
      (node (ref "U8") (pin "14") (pinfunction "PA09(I2C/AIN17/SER0:1+)_14") (pintype "bidirectional"))
    )
    (net (code "48") (name "/~{BATT_EN}") (class "Default")
      (node (ref "R40") (pin "1") (pinfunction "1_1") (pintype "passive"))
      (node (ref "R41") (pin "1") (pinfunction "1_1") (pintype "passive"))
      (node (ref "U2") (pin "P$5") (pinfunction "~{EN}_P$5") (pintype "bidirectional"))
    )
    (net (code "49") (name "/~{OLED_RES}") (class "Default")
      (node (ref "R34") (pin "2") (pinfunction "2_2") (pintype "passive"))
      (node (ref "U8") (pin "23") (pinfunction "PA14(XIN/SER2:2+)_23") (pintype "bidirectional"))
      (node (ref "U9") (pin "P$16") (pinfunction "~{RES}_P$16") (pintype "input"))
    )
    (net (code "50") (name "/~{PWR_OFF}") (class "Default")
      (node (ref "R43") (pin "1") (pinfunction "1_1") (pintype "passive"))
      (node (ref "U2") (pin "P$2") (pinfunction "~{KILL}_P$2") (pintype "bidirectional"))
      (node (ref "U8") (pin "7") (pinfunction "PB08(AIN2/SER4:0/TC4:0)_7") (pintype "bidirectional"))
    )
    (net (code "51") (name "/~{SAMD21_RST}") (class "Default")
      (node (ref "R42") (pin "1") (pinfunction "1_1") (pintype "passive"))
      (node (ref "SV2") (pin "8") (pinfunction "8_8") (pintype "passive"))
      (node (ref "U2") (pin "P$4") (pinfunction "~{INT}_P$4") (pintype "bidirectional"))
      (node (ref "U8") (pin "40") (pinfunction "~{RESET}_40") (pintype "bidirectional"))
    )
    (net (code "52") (name "/~{SYSTEM_ARM}") (class "Default")
      (node (ref "J5") (pin "TS") (pinfunction "TS_TS") (pintype "bidirectional"))
      (node (ref "R29") (pin "2") (pinfunction "2_2") (pintype "passive"))
      (node (ref "R30") (pin "2") (pinfunction "2_2") (pintype "passive"))
      (node (ref "U6") (pin "2") (pinfunction "PB3_2") (pintype "bidirectional"))
      (node (ref "U8") (pin "28") (pinfunction "PA19(SER1:3+)_28") (pintype "bidirectional"))
    )
    (net (code "53") (name "3.3V_A") (class "Default")
      (node (ref "C12") (pin "1") (pinfunction "1_1") (pintype "passive"))
      (node (ref "C14") (pin "1") (pinfunction "1_1") (pintype "passive"))
      (node (ref "C15") (pin "1") (pinfunction "1_1") (pintype "passive"))
      (node (ref "C16") (pin "1") (pinfunction "1_1") (pintype "passive"))
      (node (ref "C17") (pin "1") (pinfunction "1_1") (pintype "passive"))
      (node (ref "C20") (pin "1") (pinfunction "1_1") (pintype "passive"))
      (node (ref "C22") (pin "1") (pinfunction "1_1") (pintype "passive"))
      (node (ref "C23") (pin "1") (pinfunction "1_1") (pintype "passive"))
      (node (ref "C3") (pin "1") (pinfunction "1_1") (pintype "passive"))
      (node (ref "C4") (pin "1") (pinfunction "1_1") (pintype "passive"))
      (node (ref "J6") (pin "1") (pinfunction "1_1") (pintype "passive"))
      (node (ref "R1") (pin "1") (pinfunction "1_1") (pintype "passive"))
      (node (ref "R17") (pin "1") (pinfunction "1_1") (pintype "passive"))
      (node (ref "R21") (pin "2") (pinfunction "2_2") (pintype "passive"))
      (node (ref "R30") (pin "1") (pinfunction "1_1") (pintype "passive"))
      (node (ref "R31") (pin "2") (pinfunction "2_2") (pintype "passive"))
      (node (ref "R32") (pin "2") (pinfunction "2_2") (pintype "passive"))
      (node (ref "R33") (pin "2") (pinfunction "2_2") (pintype "passive"))
      (node (ref "R34") (pin "1") (pinfunction "1_1") (pintype "passive"))
      (node (ref "R42") (pin "2") (pinfunction "2_2") (pintype "passive"))
      (node (ref "R43") (pin "2") (pinfunction "2_2") (pintype "passive"))
      (node (ref "SV2") (pin "6") (pinfunction "6_6") (pintype "passive"))
      (node (ref "TP4") (pin "TP") (pinfunction "PP_TP") (pintype "input"))
      (node (ref "U1") (pin "3") (pinfunction "VOUT_3") (pintype "power_in"))
      (node (ref "U10") (pin "1") (pinfunction "1_VCC_IO_1") (pintype "bidirectional"))
      (node (ref "U10") (pin "8") (pinfunction "8_V_BCKP_8") (pintype "bidirectional"))
      (node (ref "U10") (pin "9") (pinfunction "9_VCC_9") (pintype "bidirectional"))
      (node (ref "U5") (pin "P$1") (pinfunction "VDD_P$1") (pintype "bidirectional"))
      (node (ref "U7") (pin "1") (pinfunction "VDD_1") (pintype "power_in"))
      (node (ref "U7") (pin "4") (pinfunction "VDDIO_4") (pintype "power_in"))
      (node (ref "U8") (pin "17") (pinfunction "VDDIO_17") (pintype "bidirectional"))
      (node (ref "U8") (pin "36") (pinfunction "VDDIO_36") (pintype "bidirectional"))
      (node (ref "U8") (pin "44") (pinfunction "VDDIN_44") (pintype "bidirectional"))
      (node (ref "U8") (pin "6") (pinfunction "VDDANA_6") (pintype "bidirectional"))
      (node (ref "U9") (pin "P$2") (pinfunction "VDD_P$2") (pintype "power_in"))
    )
    (net (code "54") (name "3.3V_B") (class "Default")
      (node (ref "C10") (pin "1") (pinfunction "1_1") (pintype "passive"))
      (node (ref "C11") (pin "1") (pinfunction "1_1") (pintype "passive"))
      (node (ref "C9") (pin "1") (pinfunction "1_1") (pintype "passive"))
      (node (ref "R22") (pin "2") (pinfunction "2_2") (pintype "passive"))
      (node (ref "R29") (pin "1") (pinfunction "1_1") (pintype "passive"))
      (node (ref "SV1") (pin "2") (pinfunction "2_2") (pintype "passive"))
      (node (ref "TP6") (pin "TP") (pinfunction "PP_TP") (pintype "input"))
      (node (ref "U4") (pin "5") (pinfunction "VOUT_5") (pintype "power_in"))
      (node (ref "U6") (pin "8") (pinfunction "VCC_8") (pintype "power_in"))
    )
    (net (code "55") (name "GND") (class "Default")
      (node (ref "C1") (pin "2") (pinfunction "2_2") (pintype "passive"))
      (node (ref "C10") (pin "2") (pinfunction "2_2") (pintype "passive"))
      (node (ref "C11") (pin "2") (pinfunction "2_2") (pintype "passive"))
      (node (ref "C12") (pin "2") (pinfunction "2_2") (pintype "passive"))
      (node (ref "C13") (pin "2") (pinfunction "2_2") (pintype "passive"))
      (node (ref "C14") (pin "2") (pinfunction "2_2") (pintype "passive"))
      (node (ref "C15") (pin "2") (pinfunction "2_2") (pintype "passive"))
      (node (ref "C16") (pin "2") (pinfunction "2_2") (pintype "passive"))
      (node (ref "C17") (pin "2") (pinfunction "2_2") (pintype "passive"))
      (node (ref "C18") (pin "-") (pinfunction "-_-") (pintype "passive"))
      (node (ref "C19") (pin "1") (pinfunction "1_1") (pintype "passive"))
      (node (ref "C2") (pin "2") (pinfunction "2_2") (pintype "passive"))
      (node (ref "C20") (pin "2") (pinfunction "2_2") (pintype "passive"))
      (node (ref "C21") (pin "1") (pinfunction "1_1") (pintype "passive"))
      (node (ref "C22") (pin "2") (pinfunction "2_2") (pintype "passive"))
      (node (ref "C23") (pin "2") (pinfunction "2_2") (pintype "passive"))
      (node (ref "C3") (pin "2") (pinfunction "2_2") (pintype "passive"))
      (node (ref "C4") (pin "2") (pinfunction "2_2") (pintype "passive"))
      (node (ref "C5") (pin "2") (pinfunction "2_2") (pintype "passive"))
      (node (ref "C8") (pin "2") (pinfunction "2_2") (pintype "passive"))
      (node (ref "D2") (pin "A") (pinfunction "A_A") (pintype "passive"))
      (node (ref "D6") (pin "A") (pinfunction "A_A") (pintype "passive"))
      (node (ref "J1") (pin "P$2") (pinfunction "P$2_P$2") (pintype "bidirectional"))
      (node (ref "J2") (pin "4") (pinfunction "GND_4") (pintype "bidirectional"))
      (node (ref "J3") (pin "P$2") (pinfunction "P$2_P$2") (pintype "bidirectional"))
      (node (ref "J4") (pin "4") (pinfunction "GND_4") (pintype "bidirectional"))
      (node (ref "J5") (pin "T") (pinfunction "T_T") (pintype "bidirectional"))
      (node (ref "J6") (pin "5") (pinfunction "5_5") (pintype "passive"))
      (node (ref "J7") (pin "5") (pinfunction "5_5") (pintype "passive"))
      (node (ref "J7") (pin "6") (pinfunction "6_6") (pintype "passive"))
      (node (ref "LED1") (pin "C") (pinfunction "C_C") (pintype "passive"))
      (node (ref "LED2") (pin "C") (pinfunction "C_C") (pintype "passive"))
      (node (ref "LED3") (pin "C") (pinfunction "C_C") (pintype "passive"))
      (node (ref "LED4") (pin "C") (pinfunction "C_C") (pintype "passive"))
      (node (ref "PB1") (pin "1") (pinfunction "1_1") (pintype "bidirectional"))
      (node (ref "Q2") (pin "1") (pinfunction "GND_1") (pintype "power_in"))
      (node (ref "Q3") (pin "1") (pinfunction "GND_1") (pintype "power_in"))
      (node (ref "Q4") (pin "4") (pinfunction "S_4") (pintype "passive"))
      (node (ref "Q5") (pin "1") (pinfunction "GND_1") (pintype "power_in"))
      (node (ref "R11") (pin "2") (pinfunction "2_2") (pintype "passive"))
      (node (ref "R13") (pin "2") (pinfunction "2_2") (pintype "passive"))
      (node (ref "R14") (pin "1") (pinfunction "1_1") (pintype "passive"))
      (node (ref "R20") (pin "2") (pinfunction "2_2") (pintype "passive"))
      (node (ref "R23") (pin "1") (pinfunction "1_1") (pintype "passive"))
      (node (ref "R25") (pin "2") (pinfunction "2_2") (pintype "passive"))
      (node (ref "R26") (pin "2") (pinfunction "2_2") (pintype "passive"))
      (node (ref "R27") (pin "1") (pinfunction "1_1") (pintype "passive"))
      (node (ref "R3") (pin "2") (pinfunction "2_2") (pintype "passive"))
      (node (ref "SV1") (pin "6") (pinfunction "6_6") (pintype "passive"))
      (node (ref "SV2") (pin "1") (pinfunction "1_1") (pintype "passive"))
      (node (ref "SV2") (pin "2") (pinfunction "2_2") (pintype "passive"))
      (node (ref "SV2") (pin "3") (pinfunction "3_3") (pintype "passive"))
      (node (ref "SV2") (pin "4") (pinfunction "4_4") (pintype "passive"))
      (node (ref "T2") (pin "2") (pinfunction "E_2") (pintype "passive"))
      (node (ref "TP7") (pin "TP") (pinfunction "PP_TP") (pintype "input"))
      (node (ref "U1") (pin "2") (pinfunction "GND_2") (pintype "power_in"))
      (node (ref "U10") (pin "10") (pinfunction "10_GND_10") (pintype "bidirectional"))
      (node (ref "U10") (pin "11") (pinfunction "11_GND_11") (pintype "bidirectional"))
      (node (ref "U10") (pin "12") (pinfunction "12_GND_12") (pintype "bidirectional"))
      (node (ref "U10") (pin "13") (pinfunction "13_GND_13") (pintype "bidirectional"))
      (node (ref "U10") (pin "14") (pinfunction "14_GND_14") (pintype "bidirectional"))
      (node (ref "U10") (pin "15") (pinfunction "15_GND_15") (pintype "bidirectional"))
      (node (ref "U10") (pin "18") (pinfunction "18_GND_18") (pintype "bidirectional"))
      (node (ref "U10") (pin "19") (pinfunction "19_GND_19") (pintype "bidirectional"))
      (node (ref "U10") (pin "21") (pinfunction "21_GND_21") (pintype "bidirectional"))
      (node (ref "U10") (pin "22") (pinfunction "22_GND_22") (pintype "bidirectional"))
      (node (ref "U10") (pin "27") (pinfunction "27_GND_27") (pintype "bidirectional"))
      (node (ref "U10") (pin "31") (pinfunction "31_GND_31") (pintype "bidirectional"))
      (node (ref "U10") (pin "4") (pinfunction "4_GND_4") (pintype "bidirectional"))
      (node (ref "U10") (pin "5") (pinfunction "5_GND_5") (pintype "bidirectional"))
      (node (ref "U2") (pin "P$1") (pinfunction "ON_P$1") (pintype "bidirectional"))
      (node (ref "U2") (pin "P$7") (pinfunction "GND_P$7") (pintype "bidirectional"))
      (node (ref "U4") (pin "2") (pinfunction "GND_2") (pintype "power_in"))
      (node (ref "U5") (pin "P$3") (pinfunction "GND_P$3") (pintype "bidirectional"))
      (node (ref "U6") (pin "4") (pinfunction "GND_4") (pintype "power_in"))
      (node (ref "U7") (pin "3") (pinfunction "GND_3") (pintype "power_in"))
      (node (ref "U8") (pin "18") (pinfunction "GND_18") (pintype "bidirectional"))
      (node (ref "U8") (pin "35") (pinfunction "GND_35") (pintype "bidirectional"))
      (node (ref "U8") (pin "42") (pinfunction "GND_42") (pintype "bidirectional"))
      (node (ref "U8") (pin "5") (pinfunction "GNDANA_5") (pintype "bidirectional"))
      (node (ref "U9") (pin "P$1") (pinfunction "GND_P$1") (pintype "power_in"))
      (node (ref "U9") (pin "P$10") (pinfunction "D3_P$10") (pintype "bidirectional"))
      (node (ref "U9") (pin "P$11") (pinfunction "D4_P$11") (pintype "bidirectional"))
      (node (ref "U9") (pin "P$12") (pinfunction "D5_P$12") (pintype "bidirectional"))
      (node (ref "U9") (pin "P$13") (pinfunction "D6_P$13") (pintype "bidirectional"))
      (node (ref "U9") (pin "P$14") (pinfunction "D7_P$14") (pintype "bidirectional"))
      (node (ref "U9") (pin "P$15") (pinfunction "~{CS}_P$15") (pintype "input"))
      (node (ref "U9") (pin "P$17") (pinfunction "BS0_P$17") (pintype "input"))
      (node (ref "U9") (pin "P$18") (pinfunction "BS1_P$18") (pintype "input"))
      (node (ref "U9") (pin "P$19") (pinfunction "BS2_P$19") (pintype "input"))
      (node (ref "U9") (pin "P$20") (pinfunction "GND2_P$20") (pintype "power_in"))
      (node (ref "U9") (pin "P$3") (pinfunction "REGVDD_P$3") (pintype "power_in"))
      (node (ref "U9") (pin "P$4") (pinfunction "D/C_P$4") (pintype "bidirectional"))
      (node (ref "U9") (pin "P$5") (pinfunction "R/W_P$5") (pintype "input"))
      (node (ref "U9") (pin "P$6") (pinfunction "E_P$6") (pintype "input"))
      (node (ref "X4") (pin "5") (pinfunction "5_5") (pintype "passive"))
    )
    (net (code "56") (name "Net-(LED1-PadA)") (class "Default")
      (node (ref "LED1") (pin "A") (pinfunction "A_A") (pintype "passive"))
      (node (ref "R9") (pin "1") (pinfunction "1_1") (pintype "passive"))
    )
    (net (code "57") (name "Net-(LED2-PadA)") (class "Default")
      (node (ref "LED2") (pin "A") (pinfunction "A_A") (pintype "passive"))
      (node (ref "R19") (pin "1") (pinfunction "1_1") (pintype "passive"))
    )
    (net (code "58") (name "Net-(LED3-PadA)") (class "Default")
      (node (ref "LED3") (pin "A") (pinfunction "A_A") (pintype "passive"))
      (node (ref "R21") (pin "1") (pinfunction "1_1") (pintype "passive"))
    )
    (net (code "59") (name "Net-(LED4-PadA)") (class "Default")
      (node (ref "LED4") (pin "A") (pinfunction "A_A") (pintype "passive"))
      (node (ref "R22") (pin "1") (pinfunction "1_1") (pintype "passive"))
    )
    (net (code "60") (name "Net-(Q1-PadG)") (class "Default")
      (node (ref "Q1") (pin "G") (pinfunction "G_G") (pintype "bidirectional"))
      (node (ref "R40") (pin "2") (pinfunction "2_2") (pintype "passive"))
    )
    (net (code "61") (name "Net-(Q2-IS)") (class "Default")
      (node (ref "Q2") (pin "4") (pinfunction "IS_4") (pintype "output"))
      (node (ref "R14") (pin "2") (pinfunction "2_2") (pintype "passive"))
    )
    (net (code "62") (name "Net-(Q3-IS)") (class "Default")
      (node (ref "Q3") (pin "4") (pinfunction "IS_4") (pintype "output"))
      (node (ref "R23") (pin "2") (pinfunction "2_2") (pintype "passive"))
    )
    (net (code "63") (name "Net-(Q4-D6)") (class "Default")
      (node (ref "Q4") (pin "1") (pinfunction "D_1") (pintype "passive"))
      (node (ref "Q4") (pin "2") (pinfunction "D_2") (pintype "passive"))
      (node (ref "Q4") (pin "5") (pinfunction "D_5") (pintype "passive"))
      (node (ref "Q4") (pin "6") (pinfunction "D6_6") (pintype "passive"))
      (node (ref "R39") (pin "1") (pinfunction "1_1") (pintype "passive"))
    )
    (net (code "64") (name "Net-(Q4-G)") (class "Default")
      (node (ref "Q4") (pin "3") (pinfunction "G_3") (pintype "passive"))
      (node (ref "R24") (pin "1") (pinfunction "1_1") (pintype "passive"))
      (node (ref "R25") (pin "1") (pinfunction "1_1") (pintype "passive"))
    )
    (net (code "65") (name "Net-(Q5-IS)") (class "Default")
      (node (ref "Q5") (pin "4") (pinfunction "IS_4") (pintype "output"))
      (node (ref "R27") (pin "2") (pinfunction "2_2") (pintype "passive"))
    )
    (net (code "66") (name "Net-(Q6-PadG)") (class "Default")
      (node (ref "Q6") (pin "G") (pinfunction "G_G") (pintype "bidirectional"))
      (node (ref "R41") (pin "2") (pinfunction "2_2") (pintype "passive"))
    )
    (net (code "67") (name "Net-(R5-Pad2)") (class "Default")
      (node (ref "R5") (pin "2") (pinfunction "2_2") (pintype "passive"))
      (node (ref "R6") (pin "1") (pinfunction "1_1") (pintype "passive"))
    )
    (net (code "68") (name "Net-(R6-Pad2)") (class "Default")
      (node (ref "R6") (pin "2") (pinfunction "2_2") (pintype "passive"))
      (node (ref "R7") (pin "1") (pinfunction "1_1") (pintype "passive"))
    )
    (net (code "69") (name "Net-(R7-Pad2)") (class "Default")
      (node (ref "R7") (pin "2") (pinfunction "2_2") (pintype "passive"))
      (node (ref "R8") (pin "1") (pinfunction "1_1") (pintype "passive"))
    )
    (net (code "70") (name "Net-(R12-Pad1)") (class "Default")
      (node (ref "R12") (pin "1") (pinfunction "1_1") (pintype "passive"))
      (node (ref "R8") (pin "2") (pinfunction "2_2") (pintype "passive"))
    )
    (net (code "71") (name "Net-(R12-Pad2)") (class "Default")
      (node (ref "R12") (pin "2") (pinfunction "2_2") (pintype "passive"))
      (node (ref "R15") (pin "2") (pinfunction "2_2") (pintype "passive"))
    )
    (net (code "72") (name "Net-(R15-Pad1)") (class "Default")
      (node (ref "R15") (pin "1") (pinfunction "1_1") (pintype "passive"))
      (node (ref "R16") (pin "2") (pinfunction "2_2") (pintype "passive"))
    )
    (net (code "73") (name "Net-(R16-Pad1)") (class "Default")
      (node (ref "R16") (pin "1") (pinfunction "1_1") (pintype "passive"))
      (node (ref "R37") (pin "2") (pinfunction "2_2") (pintype "passive"))
    )
    (net (code "74") (name "Net-(R37-Pad1)") (class "Default")
      (node (ref "R37") (pin "1") (pinfunction "1_1") (pintype "passive"))
      (node (ref "R38") (pin "2") (pinfunction "2_2") (pintype "passive"))
    )
    (net (code "75") (name "Net-(R38-Pad1)") (class "Default")
      (node (ref "R38") (pin "1") (pinfunction "1_1") (pintype "passive"))
      (node (ref "R39") (pin "2") (pinfunction "2_2") (pintype "passive"))
    )
    (net (code "76") (name "Net-(T2-B)") (class "Default")
      (node (ref "R28") (pin "1") (pinfunction "1_1") (pintype "passive"))
      (node (ref "T2") (pin "1") (pinfunction "B_1") (pintype "passive"))
    )
    (net (code "77") (name "Net-(T2-C)") (class "Default")
      (node (ref "LS1") (pin "-") (pinfunction "-_-") (pintype "bidirectional"))
      (node (ref "T2") (pin "3") (pinfunction "C_3") (pintype "passive"))
    )
    (net (code "78") (name "Net-(U2-V_IN)") (class "Default")
      (node (ref "C5") (pin "1") (pinfunction "1_1") (pintype "passive"))
      (node (ref "D3") (pin "C") (pinfunction "C_C") (pintype "bidirectional"))
      (node (ref "D5") (pin "C") (pinfunction "C_C") (pintype "bidirectional"))
      (node (ref "U2") (pin "P$6") (pinfunction "V_IN_P$6") (pintype "bidirectional"))
    )
    (net (code "79") (name "Net-(U2-~{PB})") (class "Default")
      (node (ref "PB1") (pin "3") (pinfunction "3_3") (pintype "bidirectional"))
      (node (ref "U2") (pin "P$8") (pinfunction "~{PB}_P$8") (pintype "bidirectional"))
    )
    (net (code "80") (name "Net-(U4-BYP)") (class "Default")
      (node (ref "C9") (pin "2") (pinfunction "2_2") (pintype "passive"))
      (node (ref "U4") (pin "4") (pinfunction "BYP_4") (pintype "passive"))
    )
    (net (code "81") (name "Net-(U7-CAP)") (class "Default")
      (node (ref "C13") (pin "1") (pinfunction "1_1") (pintype "passive"))
      (node (ref "U7") (pin "2") (pinfunction "CAP_2") (pintype "power_in"))
    )
    (net (code "82") (name "Net-(U8-PA00(XIN32{slash}SER1:0{slash}TC2:0))") (class "Default")
      (node (ref "C19") (pin "2") (pinfunction "2_2") (pintype "passive"))
      (node (ref "U8") (pin "1") (pinfunction "PA00(XIN32/SER1:0/TC2:0)_1") (pintype "bidirectional"))
      (node (ref "X3") (pin "P$1") (pinfunction "P1_P$1") (pintype "bidirectional"))
    )
    (net (code "83") (name "Net-(U8-PA01(XOUT32{slash}SER1:1{slash}TC2:1))") (class "Default")
      (node (ref "C21") (pin "2") (pinfunction "2_2") (pintype "passive"))
      (node (ref "U8") (pin "2") (pinfunction "PA01(XOUT32/SER1:1/TC2:1)_2") (pintype "bidirectional"))
      (node (ref "X3") (pin "P$4") (pinfunction "P4_P$4") (pintype "bidirectional"))
    )
    (net (code "84") (name "Net-(U10-16_RF_OUT)") (class "Default")
      (node (ref "U10") (pin "16") (pinfunction "16_RF_OUT_16") (pintype "bidirectional"))
      (node (ref "U10") (pin "17") (pinfunction "17_RF_IN_17") (pintype "bidirectional"))
    )
    (net (code "85") (name "Net-(U10-25_TXD)") (class "Default")
      (node (ref "R35") (pin "1") (pinfunction "1_1") (pintype "passive"))
      (node (ref "U10") (pin "25") (pinfunction "25_TXD_25") (pintype "bidirectional"))
    )
    (net (code "86") (name "Net-(U10-26_RXD)") (class "Default")
      (node (ref "R36") (pin "1") (pinfunction "1_1") (pintype "passive"))
      (node (ref "U10") (pin "26") (pinfunction "26_RXD_26") (pintype "bidirectional"))
    )
    (net (code "87") (name "unconnected-(J5-PadRS)") (class "Default")
      (node (ref "J5") (pin "RS") (pinfunction "RS_RS") (pintype "bidirectional"))
    )
    (net (code "88") (name "unconnected-(U2-TMR-PadP$3)") (class "Default")
      (node (ref "U2") (pin "P$3") (pinfunction "TMR_P$3") (pintype "bidirectional"))
    )
    (net (code "89") (name "unconnected-(U7-INT1-Pad6)") (class "Default")
      (node (ref "U7") (pin "6") (pinfunction "INT1_6") (pintype "output"))
    )
    (net (code "90") (name "unconnected-(U7-INT2-Pad5)") (class "Default")
      (node (ref "U7") (pin "5") (pinfunction "INT2_5") (pintype "output"))
    )
    (net (code "91") (name "unconnected-(U10-2_RES-Pad2)") (class "Default")
      (node (ref "U10") (pin "2") (pinfunction "2_RES_2") (pintype "bidirectional"))
    )
    (net (code "92") (name "unconnected-(U10-3_SDA{slash}~{SPI_CS}-Pad3)") (class "Default")
      (node (ref "U10") (pin "3") (pinfunction "3_SDA/~{SPI_CS}_3") (pintype "bidirectional"))
    )
    (net (code "93") (name "unconnected-(U10-6_SCL{slash}SPI_CLK-Pad6)") (class "Default")
      (node (ref "U10") (pin "6") (pinfunction "6_SCL/SPI_CLK_6") (pintype "bidirectional"))
    )
    (net (code "94") (name "unconnected-(U10-7_EXTINT-Pad7)") (class "Default")
      (node (ref "U10") (pin "7") (pinfunction "7_EXTINT_7") (pintype "bidirectional"))
    )
    (net (code "95") (name "unconnected-(U10-20_D_SEL-Pad20)") (class "Default")
      (node (ref "U10") (pin "20") (pinfunction "20_D_SEL_20") (pintype "bidirectional"))
    )
    (net (code "96") (name "unconnected-(U10-23_~{RESET}-Pad23)") (class "Default")
      (node (ref "U10") (pin "23") (pinfunction "23_~{RESET}_23") (pintype "bidirectional"))
    )
    (net (code "97") (name "unconnected-(U10-24_~{SAFEBOOT}-Pad24)") (class "Default")
      (node (ref "U10") (pin "24") (pinfunction "24_~{SAFEBOOT}_24") (pintype "bidirectional"))
    )
    (net (code "98") (name "unconnected-(U10-28_RES-Pad28)") (class "Default")
      (node (ref "U10") (pin "28") (pinfunction "28_RES_28") (pintype "bidirectional"))
    )
    (net (code "99") (name "unconnected-(U10-29_TIMEPULSE-Pad29)") (class "Default")
      (node (ref "U10") (pin "29") (pinfunction "29_TIMEPULSE_29") (pintype "bidirectional"))
    )
    (net (code "100") (name "unconnected-(U10-30_LNA_EN-Pad30)") (class "Default")
      (node (ref "U10") (pin "30") (pinfunction "30_LNA_EN_30") (pintype "bidirectional"))
    )
    (net (code "101") (name "unconnected-(X3-P$4-PadP$2)") (class "Default")
      (node (ref "X3") (pin "P$2") (pinfunction "P$4_P$2") (pintype "no_connect"))
    )
    (net (code "102") (name "unconnected-(X3-PadP$3)") (class "Default")
      (node (ref "X3") (pin "P$3") (pinfunction "P$3_P$3") (pintype "no_connect"))
    )
    (net (code "103") (name "unconnected-(X4-Pad4)") (class "Default")
      (node (ref "X4") (pin "4") (pinfunction "4_4") (pintype "passive"))
    )
  )
)
